# OBC_manufactured.net
KiCad netlist of a schematic drawn in EAGLE
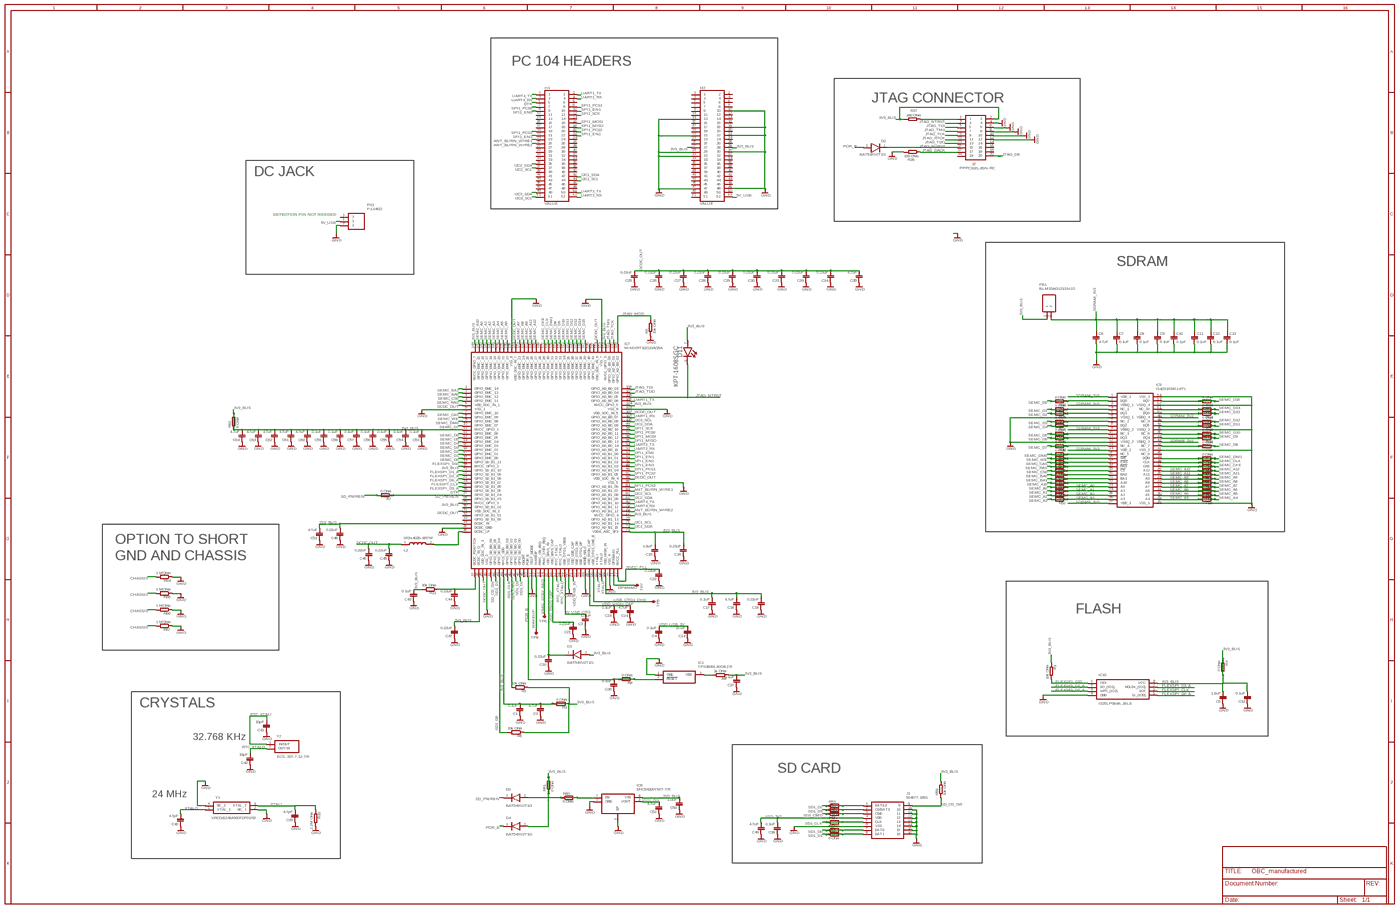
[diagram p0: schematic, sheet 1, overview]
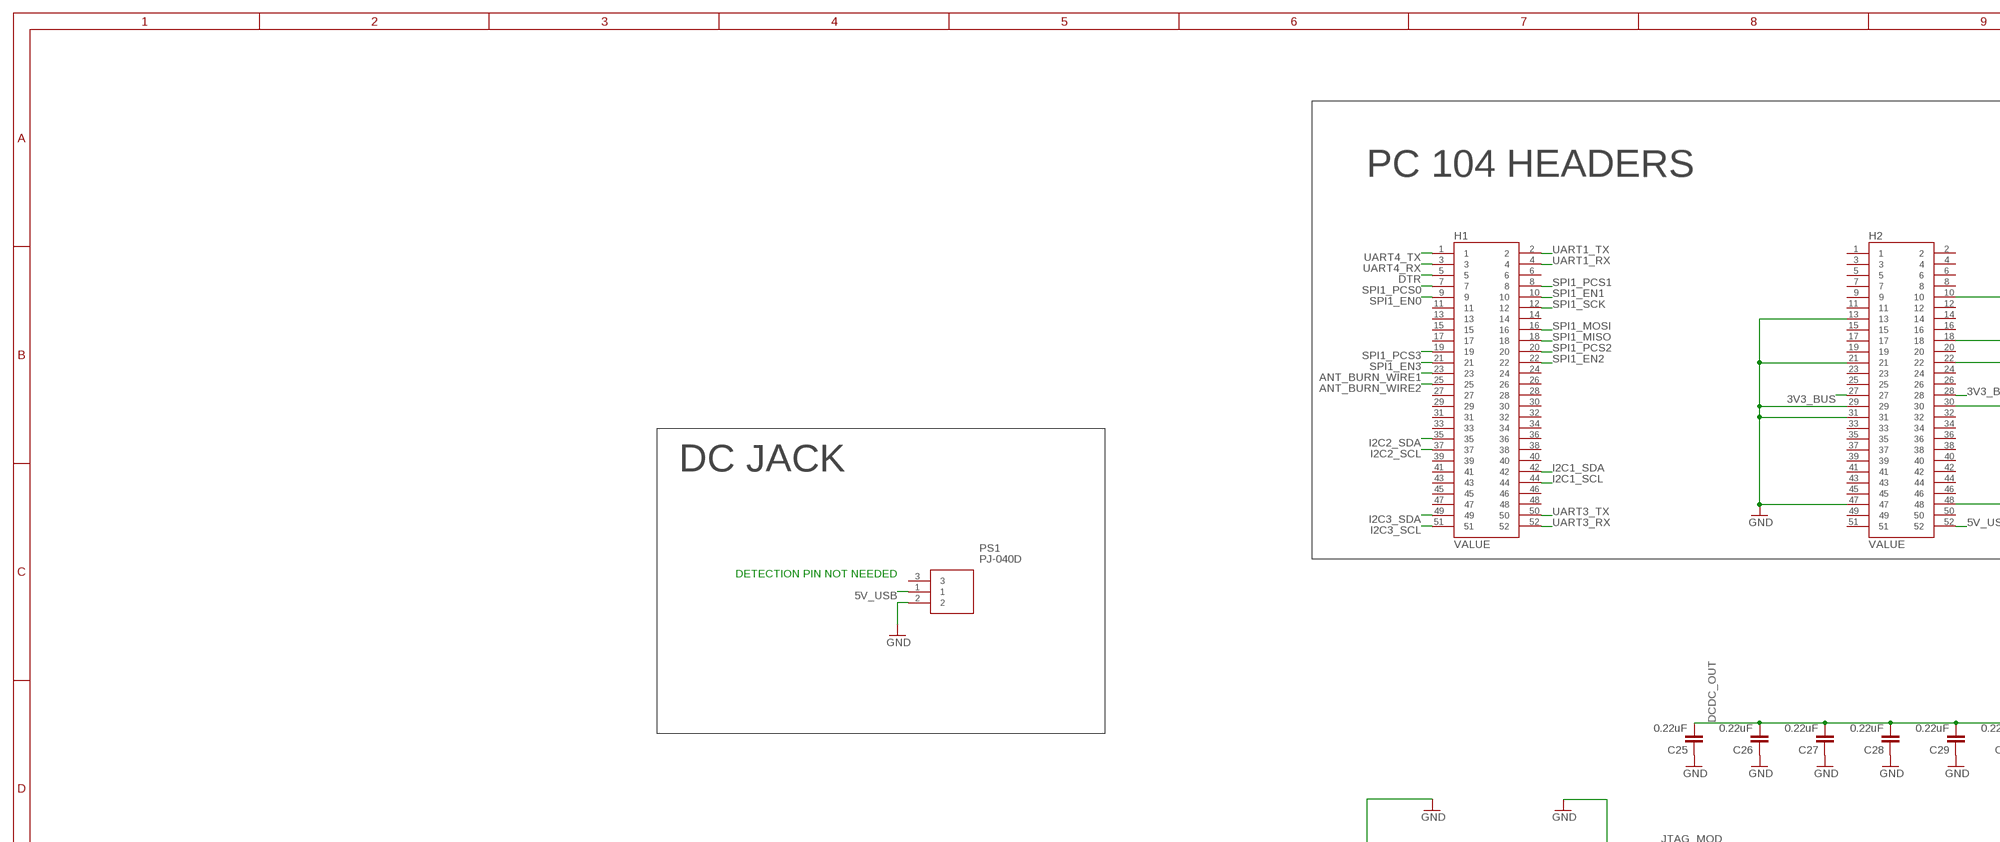
[diagram p1: schematic, sheet 1, part 1 of 4]
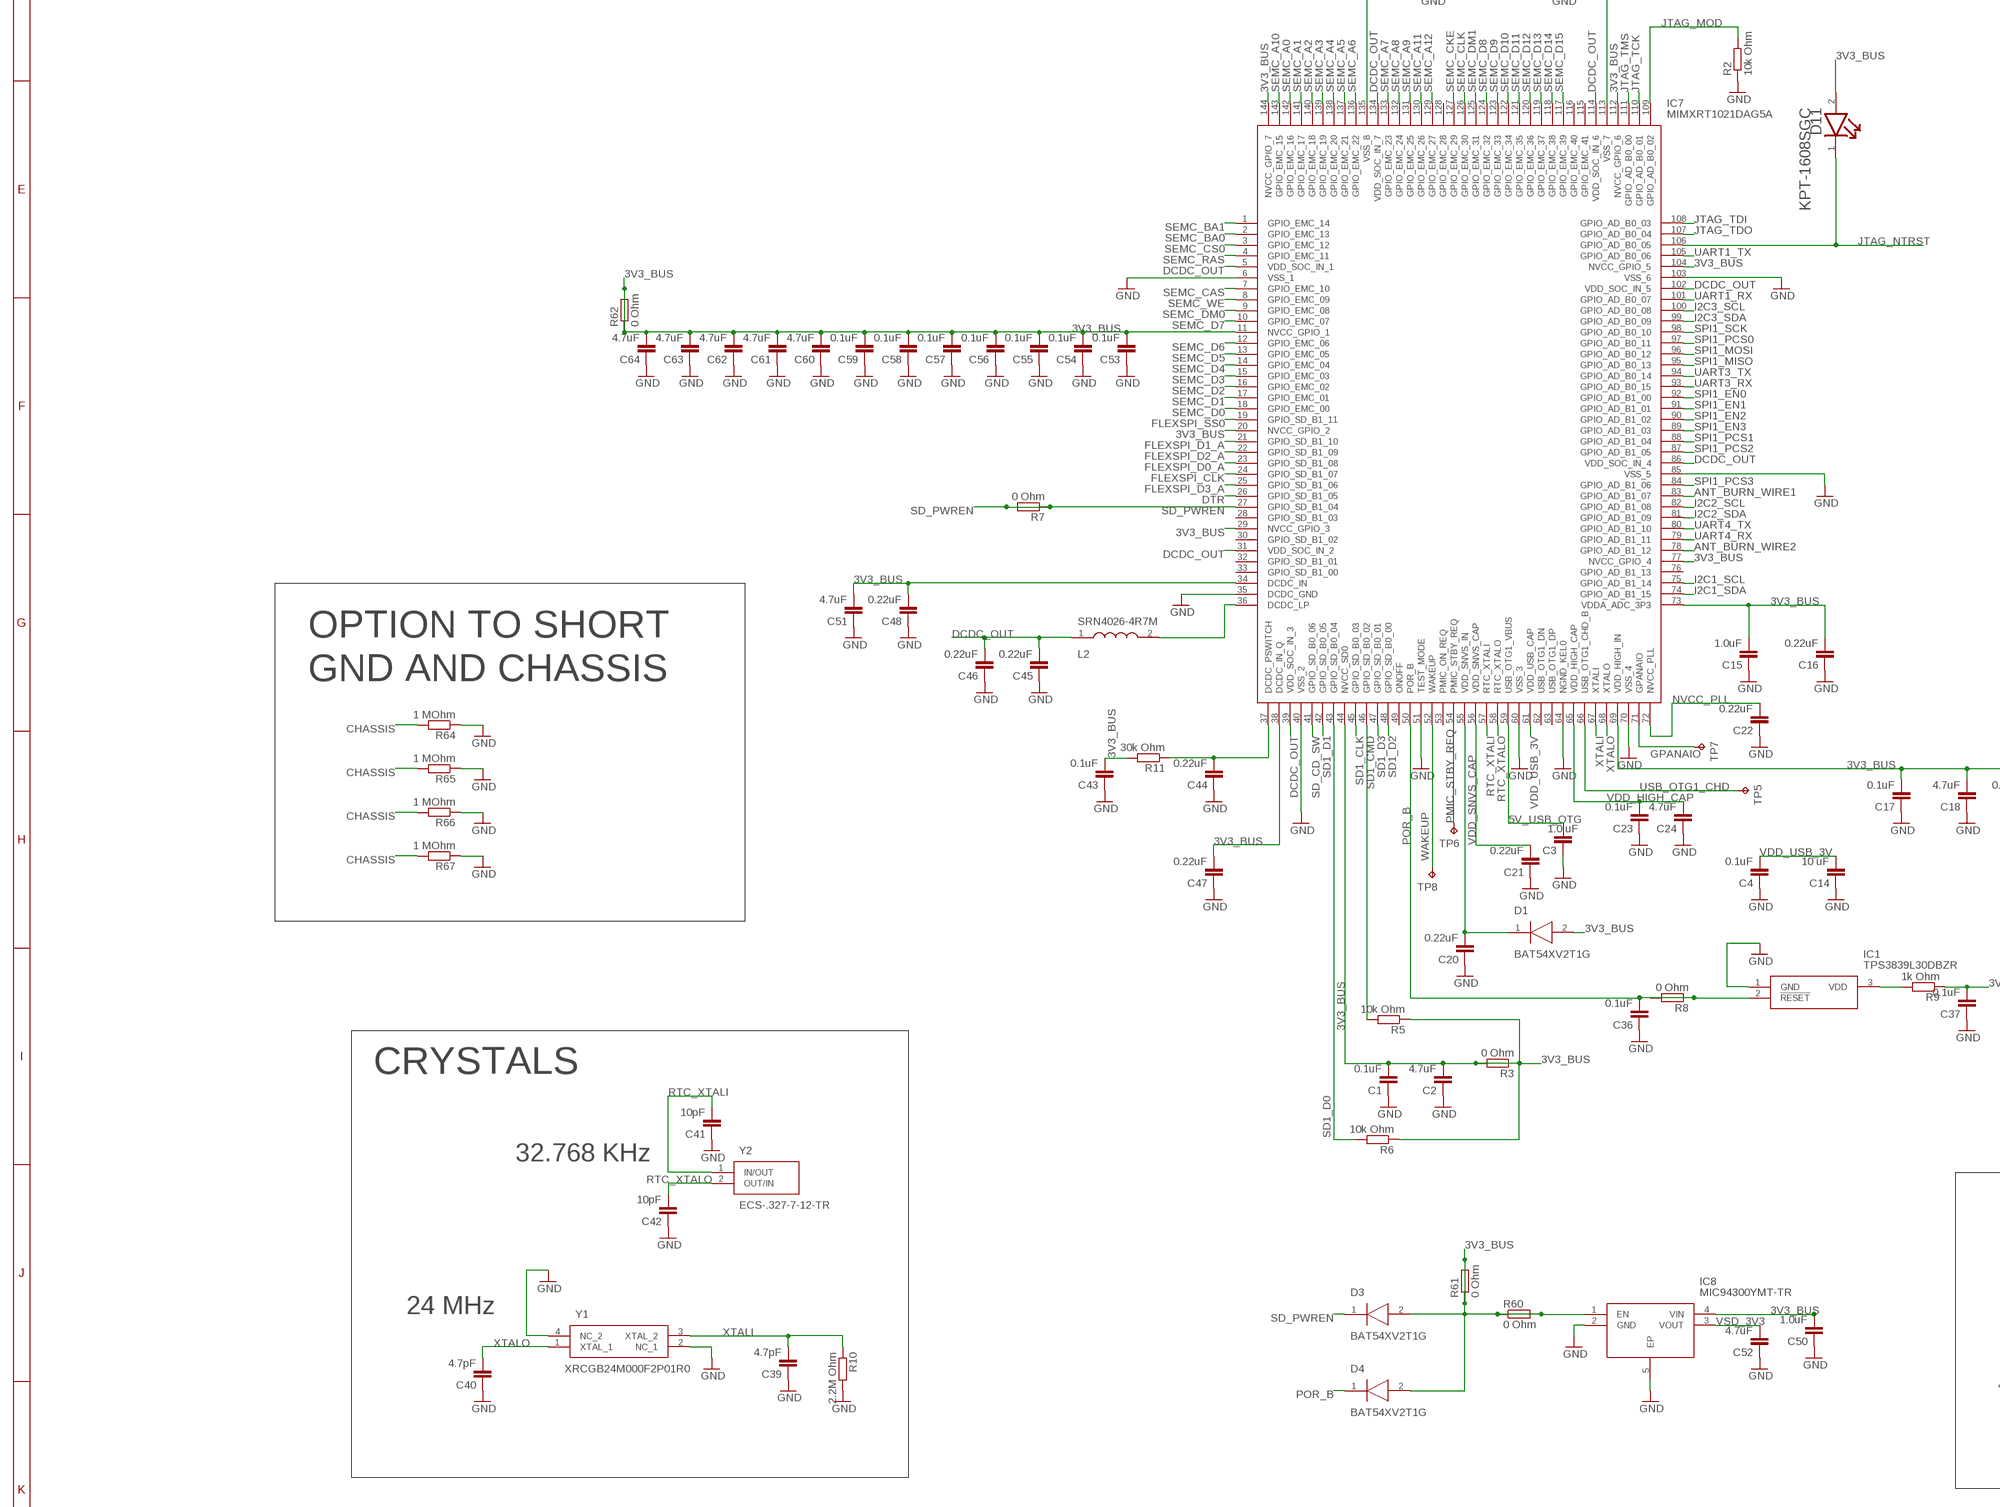
[diagram p2: schematic, sheet 1, part 2 of 4]
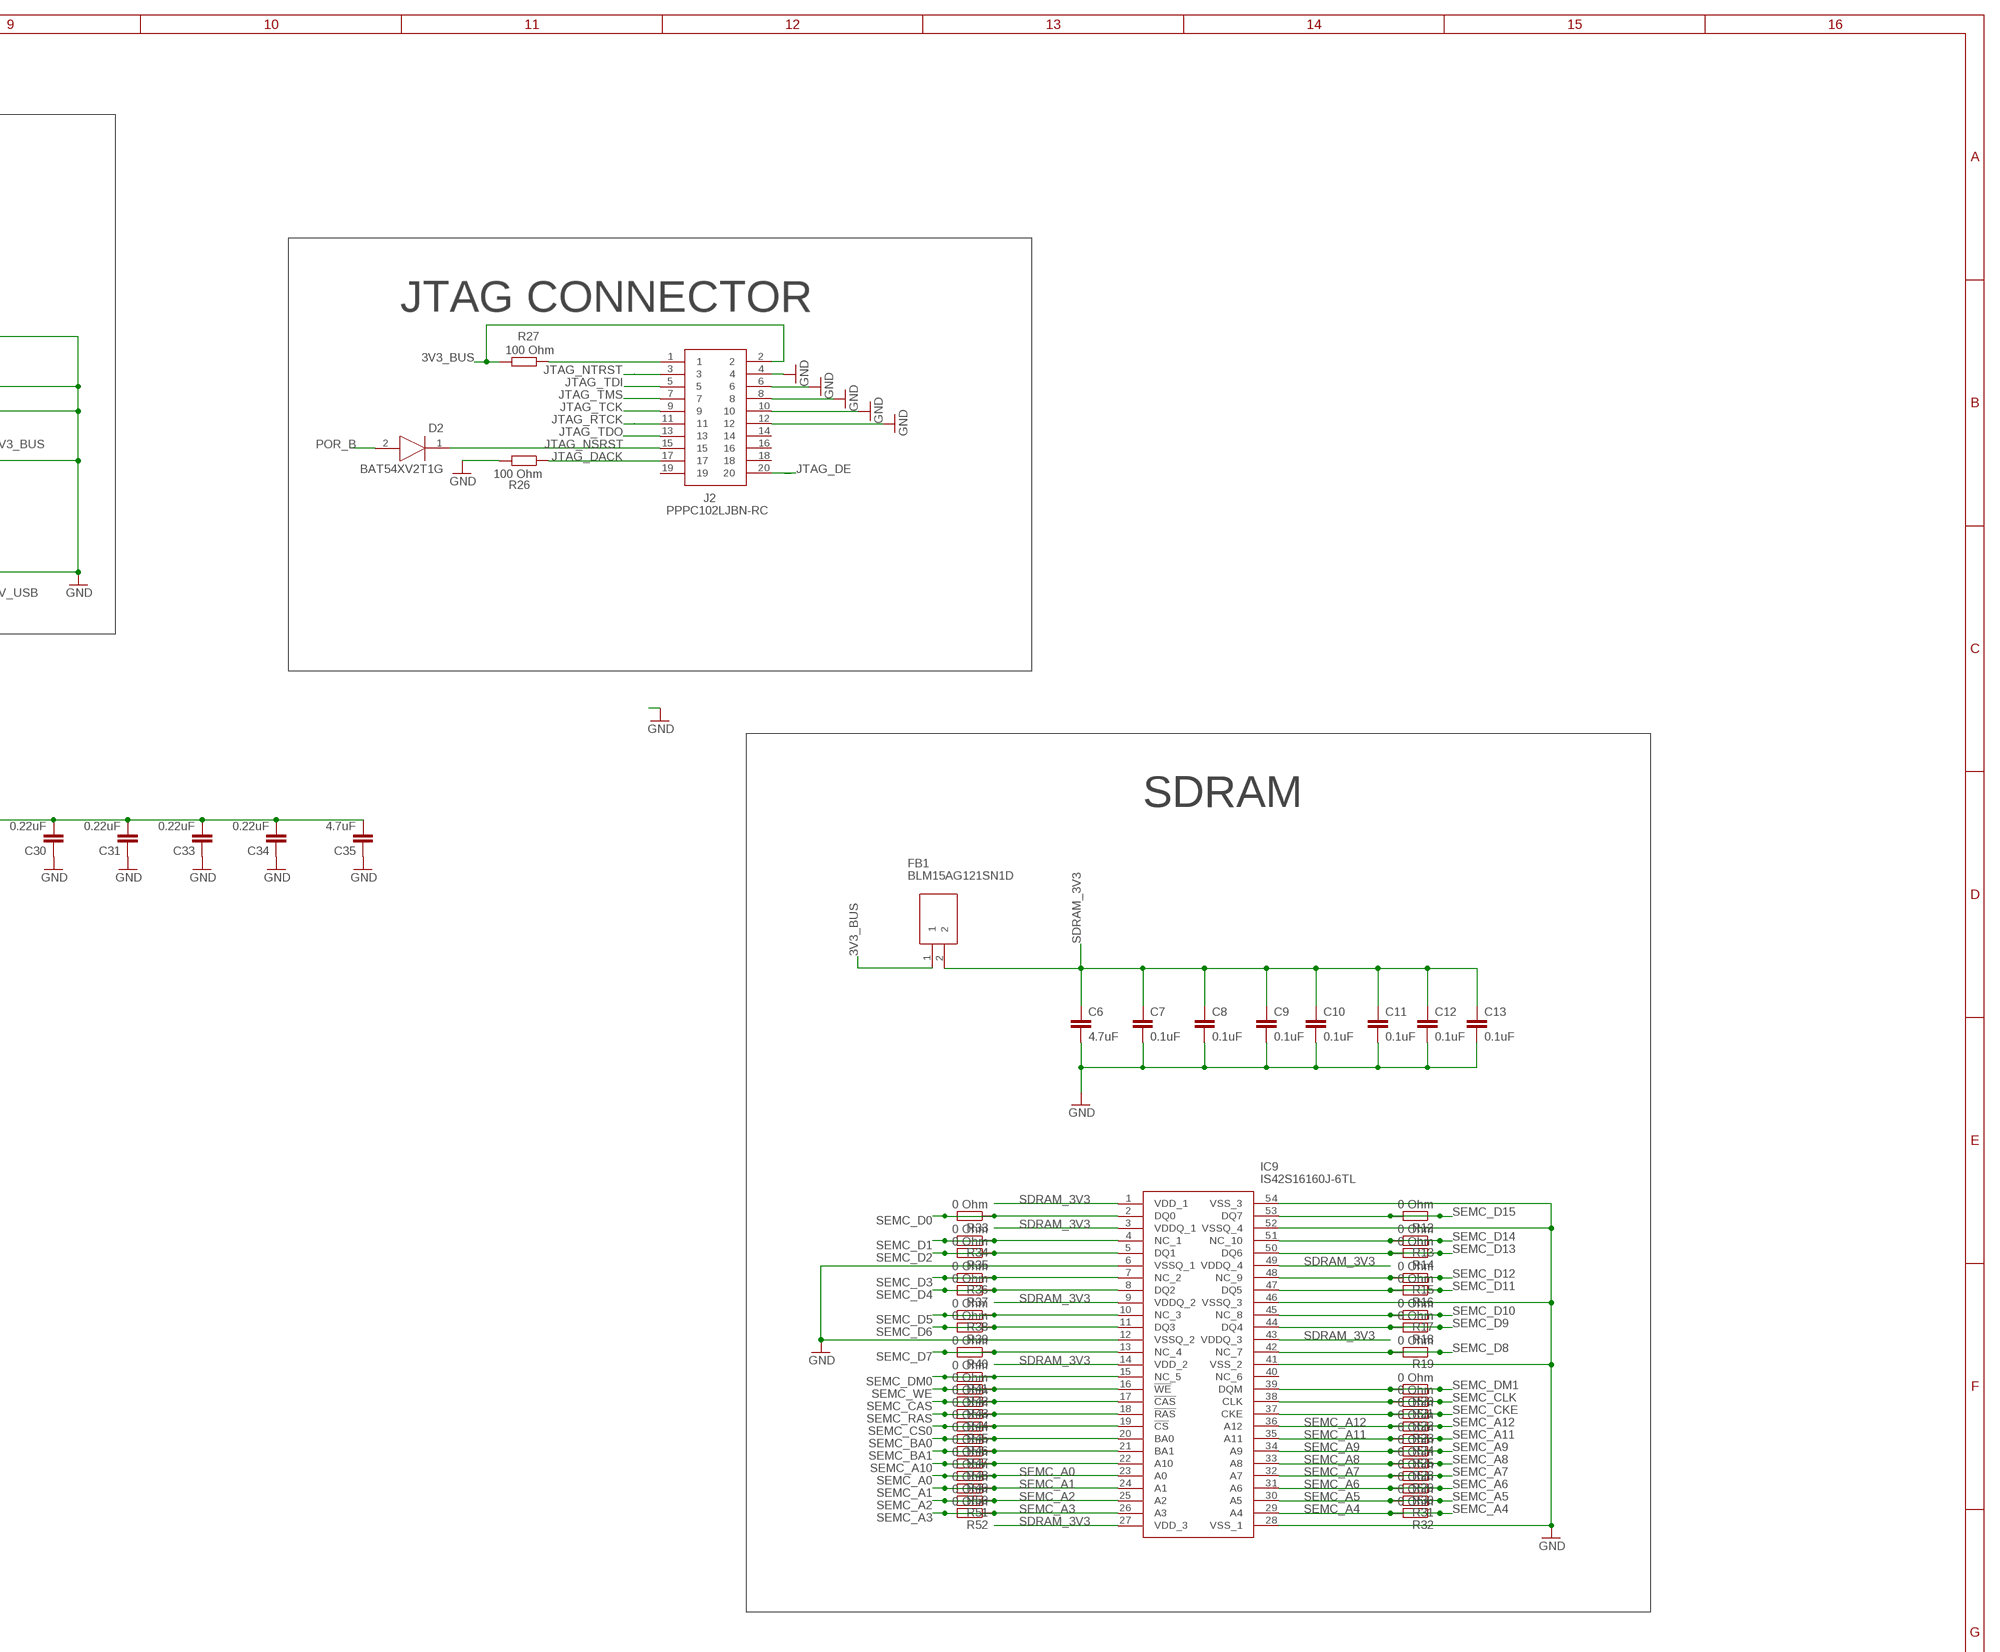
[diagram p3: schematic, sheet 1, part 3 of 4]
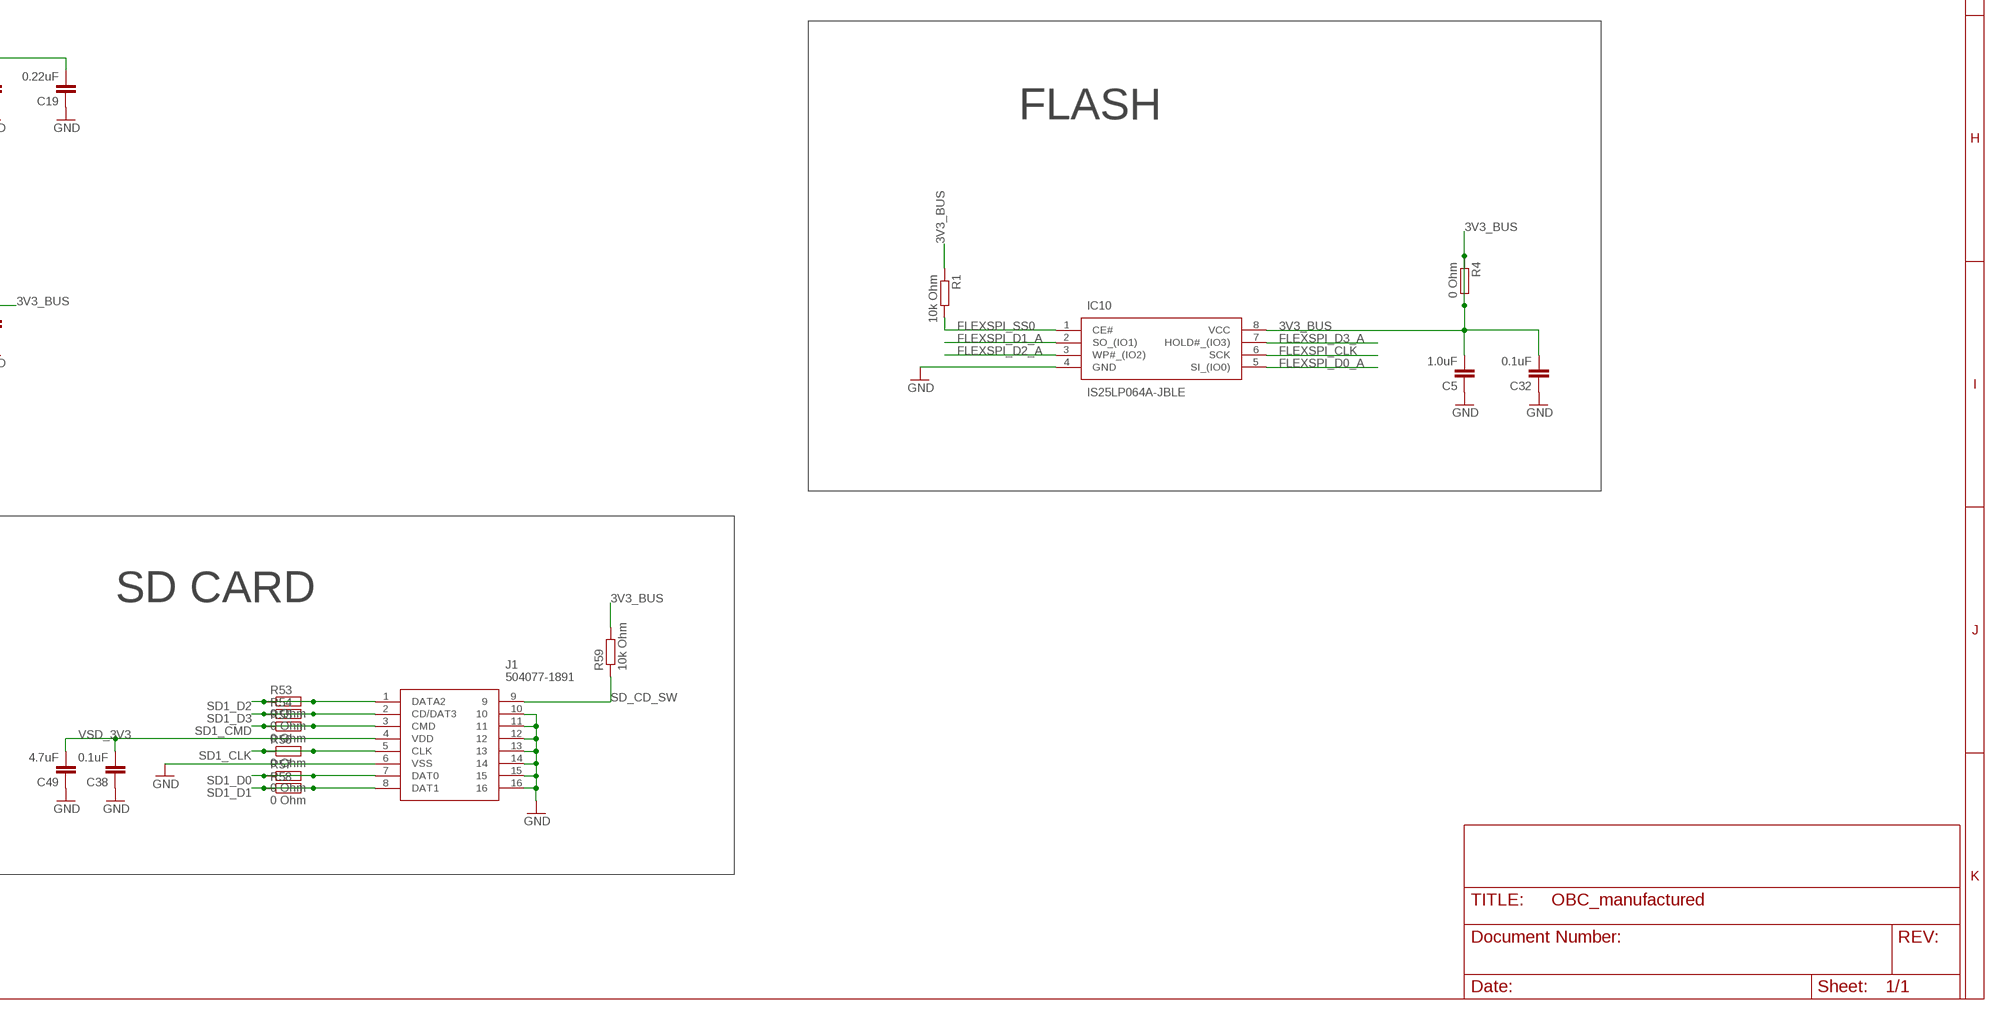
[diagram p4: schematic, sheet 1, part 4 of 4]

(export (version "E")
  (design (tool "Eeschema 10.0.6"))
  (components
    (comp (ref "C1")
      (value "0.1uF")
      (footprint "eagle-import:C0402K")
      (libsource (lib "eagle-import") (part "C-EUC0402K"))
    )
    (comp (ref "C2")
      (value "4.7uF")
      (footprint "eagle-import:C0402K")
      (libsource (lib "eagle-import") (part "C-EUC0402K"))
    )
    (comp (ref "C3")
      (value "1.0 uF")
      (footprint "eagle-import:C0402K")
      (libsource (lib "eagle-import") (part "C-EUC0402K"))
    )
    (comp (ref "C4")
      (value "0.1uF")
      (footprint "eagle-import:C0402K")
      (libsource (lib "eagle-import") (part "C-EUC0402K"))
    )
    (comp (ref "C5")
      (value "1.0uF")
      (footprint "eagle-import:C0402K")
      (libsource (lib "eagle-import") (part "C-EUC0402K"))
    )
    (comp (ref "C6")
      (value "4.7uF")
      (footprint "eagle-import:C0402K")
      (libsource (lib "eagle-import") (part "C-EUC0402K"))
    )
    (comp (ref "C7")
      (value "0.1uF")
      (footprint "eagle-import:C0402K")
      (libsource (lib "eagle-import") (part "C-EUC0402K"))
    )
    (comp (ref "C8")
      (value "0.1uF")
      (footprint "eagle-import:C0402K")
      (libsource (lib "eagle-import") (part "C-EUC0402K"))
    )
    (comp (ref "C9")
      (value "0.1uF")
      (footprint "eagle-import:C0402K")
      (libsource (lib "eagle-import") (part "C-EUC0402K"))
    )
    (comp (ref "C10")
      (value "0.1uF")
      (footprint "eagle-import:C0402K")
      (libsource (lib "eagle-import") (part "C-EUC0402K"))
    )
    (comp (ref "C11")
      (value "0.1uF")
      (footprint "eagle-import:C0402K")
      (libsource (lib "eagle-import") (part "C-EUC0402K"))
    )
    (comp (ref "C12")
      (value "0.1uF")
      (footprint "eagle-import:C0402K")
      (libsource (lib "eagle-import") (part "C-EUC0402K"))
    )
    (comp (ref "C13")
      (value "0.1uF")
      (footprint "eagle-import:C0402K")
      (libsource (lib "eagle-import") (part "C-EUC0402K"))
    )
    (comp (ref "C14")
      (value "10 uF")
      (footprint "eagle-import:C0402K")
      (libsource (lib "eagle-import") (part "C-EUC0402K"))
    )
    (comp (ref "C15")
      (value "1.0uF")
      (footprint "eagle-import:C0402K")
      (libsource (lib "eagle-import") (part "C-EUC0402K"))
    )
    (comp (ref "C16")
      (value "0.22uF")
      (footprint "eagle-import:C0402K")
      (libsource (lib "eagle-import") (part "C-EUC0402K"))
    )
    (comp (ref "C17")
      (value "0.1uF")
      (footprint "eagle-import:C0402K")
      (libsource (lib "eagle-import") (part "C-EUC0402K"))
    )
    (comp (ref "C18")
      (value "4.7uF")
      (footprint "eagle-import:C0402K")
      (libsource (lib "eagle-import") (part "C-EUC0402K"))
    )
    (comp (ref "C19")
      (value "0.22uF")
      (footprint "eagle-import:C0402K")
      (libsource (lib "eagle-import") (part "C-EUC0402K"))
    )
    (comp (ref "C20")
      (value "0.22uF")
      (footprint "eagle-import:C0402K")
      (libsource (lib "eagle-import") (part "C-EUC0402K"))
    )
    (comp (ref "C21")
      (value "0.22uF")
      (footprint "eagle-import:C0402K")
      (libsource (lib "eagle-import") (part "C-EUC0402K"))
    )
    (comp (ref "C22")
      (value "0.22uF")
      (footprint "eagle-import:C0402K")
      (libsource (lib "eagle-import") (part "C-EUC0402K"))
    )
    (comp (ref "C23")
      (value "0.1uF")
      (footprint "eagle-import:C0402K")
      (libsource (lib "eagle-import") (part "C-EUC0402K"))
    )
    (comp (ref "C24")
      (value "4.7uF")
      (footprint "eagle-import:C0402K")
      (libsource (lib "eagle-import") (part "C-EUC0402K"))
    )
    (comp (ref "C25")
      (value "0.22uF")
      (footprint "eagle-import:C0402K")
      (libsource (lib "eagle-import") (part "C-EUC0402K"))
    )
    (comp (ref "C26")
      (value "0.22uF")
      (footprint "eagle-import:C0402K")
      (libsource (lib "eagle-import") (part "C-EUC0402K"))
    )
    (comp (ref "C27")
      (value "0.22uF")
      (footprint "eagle-import:C0402K")
      (libsource (lib "eagle-import") (part "C-EUC0402K"))
    )
    (comp (ref "C28")
      (value "0.22uF")
      (footprint "eagle-import:C0402K")
      (libsource (lib "eagle-import") (part "C-EUC0402K"))
    )
    (comp (ref "C29")
      (value "0.22uF")
      (footprint "eagle-import:C0402K")
      (libsource (lib "eagle-import") (part "C-EUC0402K"))
    )
    (comp (ref "C30")
      (value "0.22uF")
      (footprint "eagle-import:C0402K")
      (libsource (lib "eagle-import") (part "C-EUC0402K"))
    )
    (comp (ref "C31")
      (value "0.22uF")
      (footprint "eagle-import:C0402K")
      (libsource (lib "eagle-import") (part "C-EUC0402K"))
    )
    (comp (ref "C32")
      (value "0.1uF")
      (footprint "eagle-import:C0402K")
      (libsource (lib "eagle-import") (part "C-EUC0402K"))
    )
    (comp (ref "C33")
      (value "0.22uF")
      (footprint "eagle-import:C0402K")
      (libsource (lib "eagle-import") (part "C-EUC0402K"))
    )
    (comp (ref "C34")
      (value "0.22uF")
      (footprint "eagle-import:C0402K")
      (libsource (lib "eagle-import") (part "C-EUC0402K"))
    )
    (comp (ref "C35")
      (value "4.7uF")
      (footprint "eagle-import:C0402K")
      (libsource (lib "eagle-import") (part "C-EUC0402K"))
    )
    (comp (ref "C36")
      (value "0.1uF")
      (footprint "eagle-import:C0402K")
      (libsource (lib "eagle-import") (part "C-EUC0402K"))
    )
    (comp (ref "C37")
      (value "0.1uF")
      (footprint "eagle-import:C0402K")
      (libsource (lib "eagle-import") (part "C-EUC0402K"))
    )
    (comp (ref "C38")
      (value "0.1uF")
      (footprint "eagle-import:C0402K")
      (libsource (lib "eagle-import") (part "C-EUC0402K"))
    )
    (comp (ref "C39")
      (value "4.7pF")
      (footprint "eagle-import:C0402K")
      (libsource (lib "eagle-import") (part "C-EUC0402K"))
    )
    (comp (ref "C40")
      (value "4.7pF")
      (footprint "eagle-import:C0402K")
      (libsource (lib "eagle-import") (part "C-EUC0402K"))
    )
    (comp (ref "C41")
      (value "10pF")
      (footprint "eagle-import:C0402K")
      (libsource (lib "eagle-import") (part "C-EUC0402K"))
    )
    (comp (ref "C42")
      (value "10pF")
      (footprint "eagle-import:C0402K")
      (libsource (lib "eagle-import") (part "C-EUC0402K"))
    )
    (comp (ref "C43")
      (value "0.1uF")
      (footprint "eagle-import:C0402K")
      (libsource (lib "eagle-import") (part "C-EUC0402K"))
    )
    (comp (ref "C44")
      (value "0.22uF")
      (footprint "eagle-import:C0402K")
      (libsource (lib "eagle-import") (part "C-EUC0402K"))
    )
    (comp (ref "C45")
      (value "0.22uF")
      (footprint "eagle-import:C0402K")
      (libsource (lib "eagle-import") (part "C-EUC0402K"))
    )
    (comp (ref "C46")
      (value "0.22uF")
      (footprint "eagle-import:C0402K")
      (libsource (lib "eagle-import") (part "C-EUC0402K"))
    )
    (comp (ref "C47")
      (value "0.22uF")
      (footprint "eagle-import:C0402K")
      (libsource (lib "eagle-import") (part "C-EUC0402K"))
    )
    (comp (ref "C48")
      (value "0.22uF")
      (footprint "eagle-import:C0402K")
      (libsource (lib "eagle-import") (part "C-EUC0402K"))
    )
    (comp (ref "C49")
      (value "4.7uF")
      (footprint "eagle-import:C0402K")
      (libsource (lib "eagle-import") (part "C-EUC0402K"))
    )
    (comp (ref "C50")
      (value "1.0uF")
      (footprint "eagle-import:C0402K")
      (libsource (lib "eagle-import") (part "C-EUC0402K"))
    )
    (comp (ref "C51")
      (value "4.7uF")
      (footprint "eagle-import:C0402K")
      (libsource (lib "eagle-import") (part "C-EUC0402K"))
    )
    (comp (ref "C52")
      (value "4.7uF")
      (footprint "eagle-import:C0402K")
      (libsource (lib "eagle-import") (part "C-EUC0402K"))
    )
    (comp (ref "C53")
      (value "0.1uF")
      (footprint "eagle-import:C0402K")
      (libsource (lib "eagle-import") (part "C-EUC0402K"))
    )
    (comp (ref "C54")
      (value "0.1uF")
      (footprint "eagle-import:C0402K")
      (libsource (lib "eagle-import") (part "C-EUC0402K"))
    )
    (comp (ref "C55")
      (value "0.1uF")
      (footprint "eagle-import:C0402K")
      (libsource (lib "eagle-import") (part "C-EUC0402K"))
    )
    (comp (ref "C56")
      (value "0.1uF")
      (footprint "eagle-import:C0402K")
      (libsource (lib "eagle-import") (part "C-EUC0402K"))
    )
    (comp (ref "C57")
      (value "0.1uF")
      (footprint "eagle-import:C0402K")
      (libsource (lib "eagle-import") (part "C-EUC0402K"))
    )
    (comp (ref "C58")
      (value "0.1uF")
      (footprint "eagle-import:C0402K")
      (libsource (lib "eagle-import") (part "C-EUC0402K"))
    )
    (comp (ref "C59")
      (value "0.1uF")
      (footprint "eagle-import:C0402K")
      (libsource (lib "eagle-import") (part "C-EUC0402K"))
    )
    (comp (ref "C60")
      (value "4.7uF")
      (footprint "eagle-import:C0402K")
      (libsource (lib "eagle-import") (part "C-EUC0402K"))
    )
    (comp (ref "C61")
      (value "4.7uF")
      (footprint "eagle-import:C0402K")
      (libsource (lib "eagle-import") (part "C-EUC0402K"))
    )
    (comp (ref "C62")
      (value "4.7uF")
      (footprint "eagle-import:C0402K")
      (libsource (lib "eagle-import") (part "C-EUC0402K"))
    )
    (comp (ref "C63")
      (value "4.7uF")
      (footprint "eagle-import:C0402K")
      (libsource (lib "eagle-import") (part "C-EUC0402K"))
    )
    (comp (ref "C64")
      (value "4.7uF")
      (footprint "eagle-import:C0402K")
      (libsource (lib "eagle-import") (part "C-EUC0402K"))
    )
    (comp (ref "D1")
      (value "BAT54XV2T1G")
      (footprint "eagle-import:SODFL1608X70N")
      (fields (field (name "MOUSER_PART_NUMBER") "863-BAT54XV2T1G"))
      (libsource (lib "eagle-import") (part "BAT54XV2T1G"))
    )
    (comp (ref "D2")
      (value "BAT54XV2T1G")
      (footprint "eagle-import:SODFL1608X70N")
      (fields (field (name "MOUSER_PART_NUMBER") "863-BAT54XV2T1G"))
      (libsource (lib "eagle-import") (part "BAT54XV2T1G"))
    )
    (comp (ref "D3")
      (value "BAT54XV2T1G")
      (footprint "eagle-import:SODFL1608X70N")
      (fields (field (name "MOUSER_PART_NUMBER") "863-BAT54XV2T1G"))
      (libsource (lib "eagle-import") (part "BAT54XV2T1G"))
    )
    (comp (ref "D4")
      (value "BAT54XV2T1G")
      (footprint "eagle-import:SODFL1608X70N")
      (fields (field (name "MOUSER_PART_NUMBER") "863-BAT54XV2T1G"))
      (libsource (lib "eagle-import") (part "BAT54XV2T1G"))
    )
    (comp (ref "D11")
      (value "KINGBRIGHT_KPT-1608SGCKINGBRIGHT_KPT-1608SGC_0_0")
      (footprint "eagle-import:KINGBRIGHT_KPT-1608SGC_0")
      (fields (field (name "MF") "Kingbright") (field (name "MPN") "KPT-1608SGC"))
      (libsource (lib "eagle-import") (part "KINGBRIGHT_KPT-1608SGCKINGBRIGHT_KPT-1608SGC_0_0"))
    )
    (comp (ref "FB1")
      (value "BLM15AG121SN1D")
      (footprint "eagle-import:NFZ15SG152SN10B")
      (fields (field (name "MOUSER_PART_NUMBER") "81-BLM15AG121SN1D"))
      (libsource (lib "eagle-import") (part "BLM15AG121SN1D"))
    )
    (comp (ref "H1")
      (value "ESQ-126-39-G-D")
      (footprint "eagle-import:SAMTEC_ESQ-126-39-G-D")
      (fields (field (name "DIGI-KEY_PART_NUMBER") "SAM10462-ND") (field (name "MF") "Samtec"))
      (libsource (lib "eagle-import") (part "ESQ-126-39-G-D"))
    )
    (comp (ref "H2")
      (value "ESQ-126-39-G-D")
      (footprint "eagle-import:SAMTEC_ESQ-126-39-G-D")
      (fields (field (name "DIGI-KEY_PART_NUMBER") "SAM10462-ND") (field (name "MF") "Samtec"))
      (libsource (lib "eagle-import") (part "ESQ-126-39-G-D"))
    )
    (comp (ref "IC1")
      (value "TPS3839L30DBZR")
      (footprint "eagle-import:SOT95P237X112-3N")
      (fields (field (name "MOUSER_PART_NUMBER") "595-TPS3839L30DBZR"))
      (libsource (lib "eagle-import") (part "TPS3839L30DBZR"))
    )
    (comp (ref "IC7")
      (value "MIMXRT1021DAG5A")
      (footprint "eagle-import:QFP50P2200X2200X160-144N")
      (fields (field (name "MOUSER_PART_NUMBER") "771-MIMXRT1021DAG5A"))
      (libsource (lib "eagle-import") (part "MIMXRT1021DAG5A"))
    )
    (comp (ref "IC8")
      (value "MIC94300YMT-TR")
      (footprint "eagle-import:SON50P160X120X60-5N")
      (fields (field (name "MOUSER_PART_NUMBER") "998-MIC94300YMTTR"))
      (libsource (lib "eagle-import") (part "MIC94300YMT-TR"))
    )
    (comp (ref "IC9")
      (value "IS42S16160J-6TL")
      (footprint "eagle-import:SOP80P1176X120-54N")
      (fields (field (name "MOUSER_PART_NUMBER") "870-IS42S16160J-6TL"))
      (libsource (lib "eagle-import") (part "IS42S16160J-6TL"))
    )
    (comp (ref "IC10")
      (value "IS25LP064A-JBLE")
      (footprint "eagle-import:SOIC127P790X216-8N")
      (libsource (lib "eagle-import") (part "IS25LP064A-JBLE"))
    )
    (comp (ref "J1")
      (value "504077-1891")
      (footprint "eagle-import:5040771891")
      (fields (field (name "MOUSER_PART_NUMBER") "538-504077-1891"))
      (libsource (lib "eagle-import") (part "504077-1891"))
    )
    (comp (ref "J2")
      (value "PPPC102LJBN-RC")
      (footprint "eagle-import:RHDRRA20W60P254X254_2X10_2590X")
      (libsource (lib "eagle-import") (part "PPPC102LJBN-RC"))
    )
    (comp (ref "L2")
      (value "SRN4026-4R7M")
      (footprint "eagle-import:SRN4026")
      (fields (field (name "MOUSER_PART_NUMBER") "652-SRN4026-4R7M"))
      (libsource (lib "eagle-import") (part "SRN4026-4R7M"))
    )
    (comp (ref "PS1")
      (value "PJ-040D")
      (footprint "eagle-import:PJ040D")
      (fields (field (name "MOUSER_PART_NUMBER") "490-PJ-040D"))
      (libsource (lib "eagle-import") (part "PJ-040D"))
    )
    (comp (ref "R1")
      (value "10k Ohm")
      (footprint "eagle-import:R0402")
      (libsource (lib "eagle-import") (part "R-EU_R0402"))
    )
    (comp (ref "R2")
      (value "10k Ohm")
      (footprint "eagle-import:R0402")
      (libsource (lib "eagle-import") (part "R-EU_R0402"))
    )
    (comp (ref "R3")
      (value "0 Ohm")
      (footprint "eagle-import:R0402")
      (libsource (lib "eagle-import") (part "R-EU_R0402"))
    )
    (comp (ref "R4")
      (value "0 Ohm")
      (footprint "eagle-import:R0402")
      (libsource (lib "eagle-import") (part "R-EU_R0402"))
    )
    (comp (ref "R5")
      (value "10k Ohm")
      (footprint "eagle-import:R0402")
      (libsource (lib "eagle-import") (part "R-EU_R0402"))
    )
    (comp (ref "R6")
      (value "10k Ohm")
      (footprint "eagle-import:R0402")
      (libsource (lib "eagle-import") (part "R-EU_R0402"))
    )
    (comp (ref "R7")
      (value "0 Ohm")
      (footprint "eagle-import:R0402")
      (libsource (lib "eagle-import") (part "R-EU_R0402"))
    )
    (comp (ref "R8")
      (value "0 Ohm")
      (footprint "eagle-import:R0402")
      (libsource (lib "eagle-import") (part "R-EU_R0402"))
    )
    (comp (ref "R9")
      (value "1k Ohm")
      (footprint "eagle-import:R0402")
      (libsource (lib "eagle-import") (part "R-EU_R0402"))
    )
    (comp (ref "R10")
      (value "2.2M Ohm")
      (footprint "eagle-import:R0402")
      (libsource (lib "eagle-import") (part "R-EU_R0402"))
    )
    (comp (ref "R11")
      (value "30k Ohm")
      (footprint "eagle-import:R0402")
      (libsource (lib "eagle-import") (part "R-EU_R0402"))
    )
    (comp (ref "R12")
      (value "0 Ohm")
      (footprint "eagle-import:R0402")
      (libsource (lib "eagle-import") (part "R-EU_R0402"))
    )
    (comp (ref "R13")
      (value "0 Ohm")
      (footprint "eagle-import:R0402")
      (libsource (lib "eagle-import") (part "R-EU_R0402"))
    )
    (comp (ref "R14")
      (value "0 Ohm")
      (footprint "eagle-import:R0402")
      (libsource (lib "eagle-import") (part "R-EU_R0402"))
    )
    (comp (ref "R15")
      (value "0 Ohm")
      (footprint "eagle-import:R0402")
      (libsource (lib "eagle-import") (part "R-EU_R0402"))
    )
    (comp (ref "R16")
      (value "0 Ohm")
      (footprint "eagle-import:R0402")
      (libsource (lib "eagle-import") (part "R-EU_R0402"))
    )
    (comp (ref "R17")
      (value "0 Ohm")
      (footprint "eagle-import:R0402")
      (libsource (lib "eagle-import") (part "R-EU_R0402"))
    )
    (comp (ref "R18")
      (value "0 Ohm")
      (footprint "eagle-import:R0402")
      (libsource (lib "eagle-import") (part "R-EU_R0402"))
    )
    (comp (ref "R19")
      (value "0 Ohm")
      (footprint "eagle-import:R0402")
      (libsource (lib "eagle-import") (part "R-EU_R0402"))
    )
    (comp (ref "R20")
      (value "0 Ohm")
      (footprint "eagle-import:R0402")
      (libsource (lib "eagle-import") (part "R-EU_R0402"))
    )
    (comp (ref "R21")
      (value "0 Ohm")
      (footprint "eagle-import:R0402")
      (libsource (lib "eagle-import") (part "R-EU_R0402"))
    )
    (comp (ref "R22")
      (value "0 Ohm")
      (footprint "eagle-import:R0402")
      (libsource (lib "eagle-import") (part "R-EU_R0402"))
    )
    (comp (ref "R23")
      (value "0 Ohm")
      (footprint "eagle-import:R0402")
      (libsource (lib "eagle-import") (part "R-EU_R0402"))
    )
    (comp (ref "R24")
      (value "0 Ohm")
      (footprint "eagle-import:R0402")
      (libsource (lib "eagle-import") (part "R-EU_R0402"))
    )
    (comp (ref "R25")
      (value "0 Ohm")
      (footprint "eagle-import:R0402")
      (libsource (lib "eagle-import") (part "R-EU_R0402"))
    )
    (comp (ref "R26")
      (value "100 Ohm")
      (footprint "eagle-import:R0402")
      (libsource (lib "eagle-import") (part "R-EU_R0402"))
    )
    (comp (ref "R27")
      (value "100 Ohm")
      (footprint "eagle-import:R0402")
      (libsource (lib "eagle-import") (part "R-EU_R0402"))
    )
    (comp (ref "R28")
      (value "0 Ohm")
      (footprint "eagle-import:R0402")
      (libsource (lib "eagle-import") (part "R-EU_R0402"))
    )
    (comp (ref "R29")
      (value "0 Ohm")
      (footprint "eagle-import:R0402")
      (libsource (lib "eagle-import") (part "R-EU_R0402"))
    )
    (comp (ref "R30")
      (value "0 Ohm")
      (footprint "eagle-import:R0402")
      (libsource (lib "eagle-import") (part "R-EU_R0402"))
    )
    (comp (ref "R31")
      (value "0 Ohm")
      (footprint "eagle-import:R0402")
      (libsource (lib "eagle-import") (part "R-EU_R0402"))
    )
    (comp (ref "R32")
      (value "0 Ohm")
      (footprint "eagle-import:R0402")
      (libsource (lib "eagle-import") (part "R-EU_R0402"))
    )
    (comp (ref "R33")
      (value "0 Ohm")
      (footprint "eagle-import:R0402")
      (libsource (lib "eagle-import") (part "R-EU_R0402"))
    )
    (comp (ref "R34")
      (value "0 Ohm")
      (footprint "eagle-import:R0402")
      (libsource (lib "eagle-import") (part "R-EU_R0402"))
    )
    (comp (ref "R35")
      (value "0 Ohm")
      (footprint "eagle-import:R0402")
      (libsource (lib "eagle-import") (part "R-EU_R0402"))
    )
    (comp (ref "R36")
      (value "0 Ohm")
      (footprint "eagle-import:R0402")
      (libsource (lib "eagle-import") (part "R-EU_R0402"))
    )
    (comp (ref "R37")
      (value "0 Ohm")
      (footprint "eagle-import:R0402")
      (libsource (lib "eagle-import") (part "R-EU_R0402"))
    )
    (comp (ref "R38")
      (value "0 Ohm")
      (footprint "eagle-import:R0402")
      (libsource (lib "eagle-import") (part "R-EU_R0402"))
    )
    (comp (ref "R39")
      (value "0 Ohm")
      (footprint "eagle-import:R0402")
      (libsource (lib "eagle-import") (part "R-EU_R0402"))
    )
    (comp (ref "R40")
      (value "0 Ohm")
      (footprint "eagle-import:R0402")
      (libsource (lib "eagle-import") (part "R-EU_R0402"))
    )
    (comp (ref "R41")
      (value "0 Ohm")
      (footprint "eagle-import:R0402")
      (libsource (lib "eagle-import") (part "R-EU_R0402"))
    )
    (comp (ref "R42")
      (value "0 Ohm")
      (footprint "eagle-import:R0402")
      (libsource (lib "eagle-import") (part "R-EU_R0402"))
    )
    (comp (ref "R43")
      (value "0 Ohm")
      (footprint "eagle-import:R0402")
      (libsource (lib "eagle-import") (part "R-EU_R0402"))
    )
    (comp (ref "R44")
      (value "0 Ohm")
      (footprint "eagle-import:R0402")
      (libsource (lib "eagle-import") (part "R-EU_R0402"))
    )
    (comp (ref "R45")
      (value "0 Ohm")
      (footprint "eagle-import:R0402")
      (libsource (lib "eagle-import") (part "R-EU_R0402"))
    )
    (comp (ref "R46")
      (value "0 Ohm")
      (footprint "eagle-import:R0402")
      (libsource (lib "eagle-import") (part "R-EU_R0402"))
    )
    (comp (ref "R47")
      (value "0 Ohm")
      (footprint "eagle-import:R0402")
      (libsource (lib "eagle-import") (part "R-EU_R0402"))
    )
    (comp (ref "R48")
      (value "0 Ohm")
      (footprint "eagle-import:R0402")
      (libsource (lib "eagle-import") (part "R-EU_R0402"))
    )
    (comp (ref "R49")
      (value "0 Ohm")
      (footprint "eagle-import:R0402")
      (libsource (lib "eagle-import") (part "R-EU_R0402"))
    )
    (comp (ref "R50")
      (value "0 Ohm")
      (footprint "eagle-import:R0402")
      (libsource (lib "eagle-import") (part "R-EU_R0402"))
    )
    (comp (ref "R51")
      (value "0 Ohm")
      (footprint "eagle-import:R0402")
      (libsource (lib "eagle-import") (part "R-EU_R0402"))
    )
    (comp (ref "R52")
      (value "0 Ohm")
      (footprint "eagle-import:R0402")
      (libsource (lib "eagle-import") (part "R-EU_R0402"))
    )
    (comp (ref "R53")
      (value "0 Ohm")
      (footprint "eagle-import:R0402")
      (libsource (lib "eagle-import") (part "R-EU_R0402"))
    )
    (comp (ref "R54")
      (value "0 Ohm")
      (footprint "eagle-import:R0402")
      (libsource (lib "eagle-import") (part "R-EU_R0402"))
    )
    (comp (ref "R55")
      (value "0 Ohm")
      (footprint "eagle-import:R0402")
      (libsource (lib "eagle-import") (part "R-EU_R0402"))
    )
    (comp (ref "R56")
      (value "0 Ohm")
      (footprint "eagle-import:R0402")
      (libsource (lib "eagle-import") (part "R-EU_R0402"))
    )
    (comp (ref "R57")
      (value "0 Ohm")
      (footprint "eagle-import:R0402")
      (libsource (lib "eagle-import") (part "R-EU_R0402"))
    )
    (comp (ref "R58")
      (value "0 Ohm")
      (footprint "eagle-import:R0402")
      (libsource (lib "eagle-import") (part "R-EU_R0402"))
    )
    (comp (ref "R59")
      (value "10k Ohm")
      (footprint "eagle-import:R0402")
      (libsource (lib "eagle-import") (part "R-EU_R0402"))
    )
    (comp (ref "R60")
      (value "0 Ohm")
      (footprint "eagle-import:R0402")
      (libsource (lib "eagle-import") (part "R-EU_R0402"))
    )
    (comp (ref "R61")
      (value "0 Ohm")
      (footprint "eagle-import:R0402")
      (libsource (lib "eagle-import") (part "R-EU_R0402"))
    )
    (comp (ref "R62")
      (value "0 Ohm")
      (footprint "eagle-import:R0402")
      (libsource (lib "eagle-import") (part "R-EU_R0402"))
    )
    (comp (ref "R64")
      (value "1 MOhm")
      (footprint "eagle-import:R0805")
      (libsource (lib "eagle-import") (part "R-EU_R0805"))
    )
    (comp (ref "R65")
      (value "1 MOhm")
      (footprint "eagle-import:R0805")
      (libsource (lib "eagle-import") (part "R-EU_R0805"))
    )
    (comp (ref "R66")
      (value "1 MOhm")
      (footprint "eagle-import:R0805")
      (libsource (lib "eagle-import") (part "R-EU_R0805"))
    )
    (comp (ref "R67")
      (value "1 MOhm")
      (footprint "eagle-import:R0805")
      (libsource (lib "eagle-import") (part "R-EU_R0805"))
    )
    (comp (ref "TP5")
      (value "TPTP06R")
      (footprint "eagle-import:TP06R")
      (libsource (lib "eagle-import") (part "TPTP06R"))
    )
    (comp (ref "TP6")
      (value "TPTP06R")
      (footprint "eagle-import:TP06R")
      (libsource (lib "eagle-import") (part "TPTP06R"))
    )
    (comp (ref "TP7")
      (value "TPTP06R")
      (footprint "eagle-import:TP06R")
      (libsource (lib "eagle-import") (part "TPTP06R"))
    )
    (comp (ref "TP8")
      (value "TPTP06R")
      (footprint "eagle-import:TP06R")
      (libsource (lib "eagle-import") (part "TPTP06R"))
    )
    (comp (ref "Y1")
      (value "XRCGB24M000F2P01R0")
      (footprint "eagle-import:XRCGB24M000F2P01R0")
      (fields (field (name "MOUSER_PART_NUMBER") "81-XRCGB24M000F2P01R"))
      (libsource (lib "eagle-import") (part "XRCGB24M000F2P01R0"))
    )
    (comp (ref "Y2")
      (value "ECS-.327-7-12-TR")
      (footprint "eagle-import:ECS327712TR")
      (fields (field (name "MOUSER_PART_NUMBER") "520-ECS-.327-7-12-TR"))
      (libsource (lib "eagle-import") (part "ECS-.327-7-12-TR"))
    )
  )
  (nets
    (net (code "1") (name "/3V3_BUS") (class "Default")
      (node (ref "C1") (pin "2") (pinfunction "2_2") (pintype "passive"))
      (node (ref "C15") (pin "2") (pinfunction "2_2") (pintype "passive"))
      (node (ref "C16") (pin "2") (pinfunction "2_2") (pintype "passive"))
      (node (ref "C17") (pin "2") (pinfunction "2_2") (pintype "passive"))
      (node (ref "C18") (pin "2") (pinfunction "2_2") (pintype "passive"))
      (node (ref "C19") (pin "2") (pinfunction "2_2") (pintype "passive"))
      (node (ref "C2") (pin "2") (pinfunction "2_2") (pintype "passive"))
      (node (ref "C32") (pin "2") (pinfunction "2_2") (pintype "passive"))
      (node (ref "C37") (pin "2") (pinfunction "2_2") (pintype "passive"))
      (node (ref "C43") (pin "2") (pinfunction "2_2") (pintype "passive"))
      (node (ref "C47") (pin "2") (pinfunction "2_2") (pintype "passive"))
      (node (ref "C48") (pin "2") (pinfunction "2_2") (pintype "passive"))
      (node (ref "C5") (pin "2") (pinfunction "2_2") (pintype "passive"))
      (node (ref "C50") (pin "2") (pinfunction "2_2") (pintype "passive"))
      (node (ref "C51") (pin "2") (pinfunction "2_2") (pintype "passive"))
      (node (ref "C53") (pin "2") (pinfunction "2_2") (pintype "passive"))
      (node (ref "C54") (pin "2") (pinfunction "2_2") (pintype "passive"))
      (node (ref "C55") (pin "2") (pinfunction "2_2") (pintype "passive"))
      (node (ref "C56") (pin "2") (pinfunction "2_2") (pintype "passive"))
      (node (ref "C57") (pin "2") (pinfunction "2_2") (pintype "passive"))
      (node (ref "C58") (pin "2") (pinfunction "2_2") (pintype "passive"))
      (node (ref "C59") (pin "2") (pinfunction "2_2") (pintype "passive"))
      (node (ref "C60") (pin "2") (pinfunction "2_2") (pintype "passive"))
      (node (ref "C61") (pin "2") (pinfunction "2_2") (pintype "passive"))
      (node (ref "C62") (pin "2") (pinfunction "2_2") (pintype "passive"))
      (node (ref "C63") (pin "2") (pinfunction "2_2") (pintype "passive"))
      (node (ref "C64") (pin "2") (pinfunction "2_2") (pintype "passive"))
      (node (ref "D1") (pin "2") (pinfunction "A_2") (pintype "bidirectional"))
      (node (ref "D11") (pin "2") (pinfunction "ANODE_2") (pintype "passive"))
      (node (ref "D3") (pin "2") (pinfunction "A_2") (pintype "bidirectional"))
      (node (ref "D4") (pin "2") (pinfunction "A_2") (pintype "bidirectional"))
      (node (ref "FB1") (pin "1") (pinfunction "1_1") (pintype "bidirectional"))
      (node (ref "H2") (pin "27") (pinfunction "27_27") (pintype "passive"))
      (node (ref "H2") (pin "28") (pinfunction "28_28") (pintype "passive"))
      (node (ref "IC10") (pin "8") (pinfunction "VCC_8") (pintype "bidirectional"))
      (node (ref "IC7") (pin "104") (pinfunction "NVCC_GPIO_5_104") (pintype "bidirectional"))
      (node (ref "IC7") (pin "11") (pinfunction "NVCC_GPIO_1_11") (pintype "bidirectional"))
      (node (ref "IC7") (pin "112") (pinfunction "NVCC_GPIO_6_112") (pintype "bidirectional"))
      (node (ref "IC7") (pin "144") (pinfunction "NVCC_GPIO_7_144") (pintype "bidirectional"))
      (node (ref "IC7") (pin "20") (pinfunction "NVCC_GPIO_2_20") (pintype "bidirectional"))
      (node (ref "IC7") (pin "29") (pinfunction "NVCC_GPIO_3_29") (pintype "bidirectional"))
      (node (ref "IC7") (pin "34") (pinfunction "DCDC_IN_34") (pintype "bidirectional"))
      (node (ref "IC7") (pin "38") (pinfunction "DCDC_IN_Q_38") (pintype "bidirectional"))
      (node (ref "IC7") (pin "44") (pinfunction "NVCC_SD0_44") (pintype "bidirectional"))
      (node (ref "IC7") (pin "69") (pinfunction "VDD_HIGH_IN_69") (pintype "bidirectional"))
      (node (ref "IC7") (pin "73") (pinfunction "VDDA_ADC_3P3_73") (pintype "bidirectional"))
      (node (ref "IC7") (pin "77") (pinfunction "NVCC_GPIO_4_77") (pintype "bidirectional"))
      (node (ref "IC8") (pin "1") (pinfunction "EN_1") (pintype "bidirectional"))
      (node (ref "IC8") (pin "4") (pinfunction "VIN_4") (pintype "bidirectional"))
      (node (ref "J2") (pin "2") (pinfunction "2_2") (pintype "bidirectional"))
      (node (ref "R1") (pin "1") (pinfunction "1_1") (pintype "passive"))
      (node (ref "R11") (pin "2") (pinfunction "2_2") (pintype "passive"))
      (node (ref "R27") (pin "1") (pinfunction "1_1") (pintype "passive"))
      (node (ref "R3") (pin "1") (pinfunction "1_1") (pintype "passive"))
      (node (ref "R3") (pin "2") (pinfunction "2_2") (pintype "passive"))
      (node (ref "R4") (pin "1") (pinfunction "1_1") (pintype "passive"))
      (node (ref "R4") (pin "2") (pinfunction "2_2") (pintype "passive"))
      (node (ref "R5") (pin "1") (pinfunction "1_1") (pintype "passive"))
      (node (ref "R59") (pin "2") (pinfunction "2_2") (pintype "passive"))
      (node (ref "R6") (pin "1") (pinfunction "1_1") (pintype "passive"))
      (node (ref "R60") (pin "1") (pinfunction "1_1") (pintype "passive"))
      (node (ref "R60") (pin "2") (pinfunction "2_2") (pintype "passive"))
      (node (ref "R61") (pin "1") (pinfunction "1_1") (pintype "passive"))
      (node (ref "R61") (pin "2") (pinfunction "2_2") (pintype "passive"))
      (node (ref "R62") (pin "1") (pinfunction "1_1") (pintype "passive"))
      (node (ref "R62") (pin "2") (pinfunction "2_2") (pintype "passive"))
      (node (ref "R9") (pin "1") (pinfunction "1_1") (pintype "passive"))
    )
    (net (code "2") (name "/5V_USB") (class "Default")
      (node (ref "H2") (pin "52") (pinfunction "52_52") (pintype "passive"))
      (node (ref "PS1") (pin "1") (pinfunction "1_1") (pintype "bidirectional"))
    )
    (net (code "3") (name "/5V_USB_OTG") (class "Default")
      (node (ref "C3") (pin "2") (pinfunction "2_2") (pintype "passive"))
      (node (ref "IC7") (pin "59") (pinfunction "USB_OTG1_VBUS_59") (pintype "bidirectional"))
    )
    (net (code "4") (name "/ANT_BURN_WIRE1") (class "Default")
      (node (ref "H1") (pin "23") (pinfunction "23_23") (pintype "passive"))
      (node (ref "IC7") (pin "83") (pinfunction "GPIO_AD_B1_07_83") (pintype "bidirectional"))
    )
    (net (code "5") (name "/ANT_BURN_WIRE2") (class "Default")
      (node (ref "H1") (pin "25") (pinfunction "25_25") (pintype "passive"))
      (node (ref "IC7") (pin "78") (pinfunction "GPIO_AD_B1_12_78") (pintype "bidirectional"))
    )
    (net (code "6") (name "/CHASSIS") (class "Default")
      (node (ref "R64") (pin "2") (pinfunction "2_2") (pintype "passive"))
      (node (ref "R65") (pin "2") (pinfunction "2_2") (pintype "passive"))
      (node (ref "R66") (pin "2") (pinfunction "2_2") (pintype "passive"))
      (node (ref "R67") (pin "2") (pinfunction "2_2") (pintype "passive"))
    )
    (net (code "7") (name "/DCDC_OUT") (class "Default")
      (node (ref "C25") (pin "2") (pinfunction "2_2") (pintype "passive"))
      (node (ref "C26") (pin "2") (pinfunction "2_2") (pintype "passive"))
      (node (ref "C27") (pin "2") (pinfunction "2_2") (pintype "passive"))
      (node (ref "C28") (pin "2") (pinfunction "2_2") (pintype "passive"))
      (node (ref "C29") (pin "2") (pinfunction "2_2") (pintype "passive"))
      (node (ref "C30") (pin "2") (pinfunction "2_2") (pintype "passive"))
      (node (ref "C31") (pin "2") (pinfunction "2_2") (pintype "passive"))
      (node (ref "C33") (pin "2") (pinfunction "2_2") (pintype "passive"))
      (node (ref "C34") (pin "2") (pinfunction "2_2") (pintype "passive"))
      (node (ref "C35") (pin "2") (pinfunction "2_2") (pintype "passive"))
      (node (ref "C45") (pin "2") (pinfunction "2_2") (pintype "passive"))
      (node (ref "C46") (pin "2") (pinfunction "2_2") (pintype "passive"))
      (node (ref "IC7") (pin "102") (pinfunction "VDD_SOC_IN_5_102") (pintype "bidirectional"))
      (node (ref "IC7") (pin "114") (pinfunction "VDD_SOC_IN_6_114") (pintype "bidirectional"))
      (node (ref "IC7") (pin "134") (pinfunction "VDD_SOC_IN_7_134") (pintype "bidirectional"))
      (node (ref "IC7") (pin "31") (pinfunction "VDD_SOC_IN_2_31") (pintype "bidirectional"))
      (node (ref "IC7") (pin "39") (pinfunction "VDD_SOC_IN_3_39") (pintype "bidirectional"))
      (node (ref "IC7") (pin "5") (pinfunction "VDD_SOC_IN_1_5") (pintype "bidirectional"))
      (node (ref "IC7") (pin "86") (pinfunction "VDD_SOC_IN_4_86") (pintype "bidirectional"))
      (node (ref "L2") (pin "1") (pinfunction "1_1") (pintype "bidirectional"))
    )
    (net (code "8") (name "/DTR") (class "Default")
      (node (ref "H1") (pin "5") (pinfunction "5_5") (pintype "passive"))
      (node (ref "IC7") (pin "26") (pinfunction "GPIO_SD_B1_05_26") (pintype "bidirectional"))
    )
    (net (code "9") (name "/FLEXSPI_CLK") (class "Default")
      (node (ref "IC10") (pin "6") (pinfunction "SCK_6") (pintype "bidirectional"))
      (node (ref "IC7") (pin "24") (pinfunction "GPIO_SD_B1_07_24") (pintype "bidirectional"))
    )
    (net (code "10") (name "/FLEXSPI_D0_A") (class "Default")
      (node (ref "IC10") (pin "5") (pinfunction "SI_(IO0)_5") (pintype "bidirectional"))
      (node (ref "IC7") (pin "23") (pinfunction "GPIO_SD_B1_08_23") (pintype "bidirectional"))
    )
    (net (code "11") (name "/FLEXSPI_D1_A") (class "Default")
      (node (ref "IC10") (pin "2") (pinfunction "SO_(IO1)_2") (pintype "bidirectional"))
      (node (ref "IC7") (pin "21") (pinfunction "GPIO_SD_B1_10_21") (pintype "bidirectional"))
    )
    (net (code "12") (name "/FLEXSPI_D2_A") (class "Default")
      (node (ref "IC10") (pin "3") (pinfunction "WP#_(IO2)_3") (pintype "bidirectional"))
      (node (ref "IC7") (pin "22") (pinfunction "GPIO_SD_B1_09_22") (pintype "bidirectional"))
    )
    (net (code "13") (name "/FLEXSPI_D3_A") (class "Default")
      (node (ref "IC10") (pin "7") (pinfunction "HOLD#_(IO3)_7") (pintype "bidirectional"))
      (node (ref "IC7") (pin "25") (pinfunction "GPIO_SD_B1_06_25") (pintype "bidirectional"))
    )
    (net (code "14") (name "/FLEXSPI_SS0") (class "Default")
      (node (ref "IC10") (pin "1") (pinfunction "CE#_1") (pintype "bidirectional"))
      (node (ref "IC7") (pin "19") (pinfunction "GPIO_SD_B1_11_19") (pintype "bidirectional"))
      (node (ref "R1") (pin "2") (pinfunction "2_2") (pintype "passive"))
    )
    (net (code "15") (name "/GPANAIO") (class "Default")
      (node (ref "IC7") (pin "71") (pinfunction "GPANAIO_71") (pintype "bidirectional"))
      (node (ref "TP7") (pin "TP") (pinfunction "TP_TP") (pintype "input"))
    )
    (net (code "16") (name "/I2C1_SCL") (class "Default")
      (node (ref "H1") (pin "44") (pinfunction "44_44") (pintype "passive"))
      (node (ref "IC7") (pin "75") (pinfunction "GPIO_AD_B1_14_75") (pintype "bidirectional"))
    )
    (net (code "17") (name "/I2C1_SDA") (class "Default")
      (node (ref "H1") (pin "42") (pinfunction "42_42") (pintype "passive"))
      (node (ref "IC7") (pin "74") (pinfunction "GPIO_AD_B1_15_74") (pintype "bidirectional"))
    )
    (net (code "18") (name "/I2C2_SCL") (class "Default")
      (node (ref "H1") (pin "37") (pinfunction "37_37") (pintype "passive"))
      (node (ref "IC7") (pin "82") (pinfunction "GPIO_AD_B1_08_82") (pintype "bidirectional"))
    )
    (net (code "19") (name "/I2C2_SDA") (class "Default")
      (node (ref "H1") (pin "35") (pinfunction "35_35") (pintype "passive"))
      (node (ref "IC7") (pin "81") (pinfunction "GPIO_AD_B1_09_81") (pintype "bidirectional"))
    )
    (net (code "20") (name "/I2C3_SCL") (class "Default")
      (node (ref "H1") (pin "51") (pinfunction "51_51") (pintype "passive"))
      (node (ref "IC7") (pin "100") (pinfunction "GPIO_AD_B0_08_100") (pintype "bidirectional"))
    )
    (net (code "21") (name "/I2C3_SDA") (class "Default")
      (node (ref "H1") (pin "49") (pinfunction "49_49") (pintype "passive"))
      (node (ref "IC7") (pin "99") (pinfunction "GPIO_AD_B0_09_99") (pintype "bidirectional"))
    )
    (net (code "22") (name "/JTAG_DACK") (class "Default")
      (node (ref "J2") (pin "17") (pinfunction "17_17") (pintype "bidirectional"))
      (node (ref "R26") (pin "1") (pinfunction "1_1") (pintype "passive"))
    )
    (net (code "23") (name "/JTAG_DE") (class "Default")
      (node (ref "J2") (pin "20") (pinfunction "20_20") (pintype "bidirectional"))
    )
    (net (code "24") (name "/JTAG_MOD") (class "Default")
      (node (ref "IC7") (pin "109") (pinfunction "GPIO_AD_B0_02_109") (pintype "bidirectional"))
      (node (ref "R2") (pin "2") (pinfunction "2_2") (pintype "passive"))
    )
    (net (code "25") (name "/JTAG_NSRST") (class "Default")
      (node (ref "D2") (pin "1") (pinfunction "K_1") (pintype "bidirectional"))
      (node (ref "J2") (pin "15") (pinfunction "15_15") (pintype "bidirectional"))
    )
    (net (code "26") (name "/JTAG_NTRST") (class "Default")
      (node (ref "D11") (pin "1") (pinfunction "CATHODE_1") (pintype "passive"))
      (node (ref "IC7") (pin "106") (pinfunction "GPIO_AD_B0_05_106") (pintype "bidirectional"))
      (node (ref "J2") (pin "3") (pinfunction "3_3") (pintype "bidirectional"))
    )
    (net (code "27") (name "/JTAG_RTCK") (class "Default")
      (node (ref "J2") (pin "11") (pinfunction "11_11") (pintype "bidirectional"))
    )
    (net (code "28") (name "/JTAG_TCK") (class "Default")
      (node (ref "IC7") (pin "110") (pinfunction "GPIO_AD_B0_01_110") (pintype "bidirectional"))
      (node (ref "J2") (pin "9") (pinfunction "9_9") (pintype "bidirectional"))
    )
    (net (code "29") (name "/JTAG_TDI") (class "Default")
      (node (ref "IC7") (pin "108") (pinfunction "GPIO_AD_B0_03_108") (pintype "bidirectional"))
      (node (ref "J2") (pin "5") (pinfunction "5_5") (pintype "bidirectional"))
    )
    (net (code "30") (name "/JTAG_TDO") (class "Default")
      (node (ref "IC7") (pin "107") (pinfunction "GPIO_AD_B0_04_107") (pintype "bidirectional"))
      (node (ref "J2") (pin "13") (pinfunction "13_13") (pintype "bidirectional"))
    )
    (net (code "31") (name "/JTAG_TMS") (class "Default")
      (node (ref "IC7") (pin "111") (pinfunction "GPIO_AD_B0_00_111") (pintype "bidirectional"))
      (node (ref "J2") (pin "7") (pinfunction "7_7") (pintype "bidirectional"))
    )
    (net (code "32") (name "/NVCC_PLL") (class "Default")
      (node (ref "C22") (pin "2") (pinfunction "2_2") (pintype "passive"))
      (node (ref "IC7") (pin "72") (pinfunction "NVCC_PLL_72") (pintype "bidirectional"))
    )
    (net (code "33") (name "/PMIC_STBY_REQ") (class "Default")
      (node (ref "IC7") (pin "54") (pinfunction "PMIC_STBY_REQ_54") (pintype "bidirectional"))
      (node (ref "TP6") (pin "TP") (pinfunction "TP_TP") (pintype "input"))
    )
    (net (code "34") (name "/POR_B") (class "Default")
      (node (ref "C36") (pin "2") (pinfunction "2_2") (pintype "passive"))
      (node (ref "D2") (pin "2") (pinfunction "A_2") (pintype "bidirectional"))
      (node (ref "D4") (pin "1") (pinfunction "K_1") (pintype "bidirectional"))
      (node (ref "IC1") (pin "2") (pinfunction "~{RESET}_2") (pintype "bidirectional"))
      (node (ref "IC7") (pin "50") (pinfunction "POR_B_50") (pintype "bidirectional"))
      (node (ref "R8") (pin "1") (pinfunction "1_1") (pintype "passive"))
      (node (ref "R8") (pin "2") (pinfunction "2_2") (pintype "passive"))
    )
    (net (code "35") (name "/RTC_XTALI") (class "Default")
      (node (ref "C41") (pin "2") (pinfunction "2_2") (pintype "passive"))
      (node (ref "IC7") (pin "57") (pinfunction "RTC_XTALI_57") (pintype "bidirectional"))
      (node (ref "Y2") (pin "1") (pinfunction "IN/OUT_1") (pintype "bidirectional"))
    )
    (net (code "36") (name "/RTC_XTALO") (class "Default")
      (node (ref "C42") (pin "2") (pinfunction "2_2") (pintype "passive"))
      (node (ref "IC7") (pin "58") (pinfunction "RTC_XTALO_58") (pintype "bidirectional"))
      (node (ref "Y2") (pin "2") (pinfunction "OUT/IN_2") (pintype "bidirectional"))
    )
    (net (code "37") (name "/SD1_CLK") (class "Default")
      (node (ref "IC7") (pin "45") (pinfunction "GPIO_SD_B0_03_45") (pintype "bidirectional"))
      (node (ref "J1") (pin "5") (pinfunction "CLK_5") (pintype "input"))
      (node (ref "R56") (pin "1") (pinfunction "1_1") (pintype "passive"))
      (node (ref "R56") (pin "2") (pinfunction "2_2") (pintype "passive"))
    )
    (net (code "38") (name "/SD1_CMD") (class "Default")
      (node (ref "IC7") (pin "46") (pinfunction "GPIO_SD_B0_02_46") (pintype "bidirectional"))
      (node (ref "J1") (pin "3") (pinfunction "CMD_3") (pintype "bidirectional"))
      (node (ref "R5") (pin "2") (pinfunction "2_2") (pintype "passive"))
      (node (ref "R55") (pin "1") (pinfunction "1_1") (pintype "passive"))
      (node (ref "R55") (pin "2") (pinfunction "2_2") (pintype "passive"))
    )
    (net (code "39") (name "/SD1_D0") (class "Default")
      (node (ref "IC7") (pin "43") (pinfunction "GPIO_SD_B0_04_43") (pintype "bidirectional"))
      (node (ref "J1") (pin "7") (pinfunction "DAT0_7") (pintype "bidirectional"))
      (node (ref "R57") (pin "1") (pinfunction "1_1") (pintype "passive"))
      (node (ref "R57") (pin "2") (pinfunction "2_2") (pintype "passive"))
      (node (ref "R6") (pin "2") (pinfunction "2_2") (pintype "passive"))
    )
    (net (code "40") (name "/SD1_D1") (class "Default")
      (node (ref "IC7") (pin "42") (pinfunction "GPIO_SD_B0_05_42") (pintype "bidirectional"))
      (node (ref "J1") (pin "8") (pinfunction "DAT1_8") (pintype "bidirectional"))
      (node (ref "R58") (pin "1") (pinfunction "1_1") (pintype "passive"))
      (node (ref "R58") (pin "2") (pinfunction "2_2") (pintype "passive"))
    )
    (net (code "41") (name "/SD1_D2") (class "Default")
      (node (ref "IC7") (pin "48") (pinfunction "GPIO_SD_B0_00_48") (pintype "bidirectional"))
      (node (ref "J1") (pin "1") (pinfunction "DATA2_1") (pintype "bidirectional"))
      (node (ref "R53") (pin "1") (pinfunction "1_1") (pintype "passive"))
      (node (ref "R53") (pin "2") (pinfunction "2_2") (pintype "passive"))
    )
    (net (code "42") (name "/SD1_D3") (class "Default")
      (node (ref "IC7") (pin "47") (pinfunction "GPIO_SD_B0_01_47") (pintype "bidirectional"))
      (node (ref "J1") (pin "2") (pinfunction "CD/DAT3_2") (pintype "bidirectional"))
      (node (ref "R54") (pin "1") (pinfunction "1_1") (pintype "passive"))
      (node (ref "R54") (pin "2") (pinfunction "2_2") (pintype "passive"))
    )
    (net (code "43") (name "/SDRAM_3V3") (class "Default")
      (node (ref "C10") (pin "1") (pinfunction "1_1") (pintype "passive"))
      (node (ref "C11") (pin "1") (pinfunction "1_1") (pintype "passive"))
      (node (ref "C12") (pin "1") (pinfunction "1_1") (pintype "passive"))
      (node (ref "C13") (pin "1") (pinfunction "1_1") (pintype "passive"))
      (node (ref "C6") (pin "1") (pinfunction "1_1") (pintype "passive"))
      (node (ref "C7") (pin "1") (pinfunction "1_1") (pintype "passive"))
      (node (ref "C8") (pin "1") (pinfunction "1_1") (pintype "passive"))
      (node (ref "C9") (pin "1") (pinfunction "1_1") (pintype "passive"))
      (node (ref "FB1") (pin "2") (pinfunction "2_2") (pintype "bidirectional"))
      (node (ref "IC9") (pin "1") (pinfunction "VDD_1_1") (pintype "bidirectional"))
      (node (ref "IC9") (pin "14") (pinfunction "VDD_2_14") (pintype "bidirectional"))
      (node (ref "IC9") (pin "27") (pinfunction "VDD_3_27") (pintype "bidirectional"))
      (node (ref "IC9") (pin "3") (pinfunction "VDDQ_1_3") (pintype "bidirectional"))
      (node (ref "IC9") (pin "43") (pinfunction "VDDQ_3_43") (pintype "bidirectional"))
      (node (ref "IC9") (pin "49") (pinfunction "VDDQ_4_49") (pintype "bidirectional"))
      (node (ref "IC9") (pin "9") (pinfunction "VDDQ_2_9") (pintype "bidirectional"))
    )
    (net (code "44") (name "/SD_CD_SW") (class "Default")
      (node (ref "IC7") (pin "41") (pinfunction "GPIO_SD_B0_06_41") (pintype "bidirectional"))
      (node (ref "J1") (pin "9") (pinfunction "9_9") (pintype "bidirectional"))
      (node (ref "R59") (pin "1") (pinfunction "1_1") (pintype "passive"))
    )
    (net (code "45") (name "/SD_PWREN") (class "Default")
      (node (ref "D3") (pin "1") (pinfunction "K_1") (pintype "bidirectional"))
      (node (ref "IC7") (pin "27") (pinfunction "GPIO_SD_B1_04_27") (pintype "bidirectional"))
      (node (ref "R7") (pin "1") (pinfunction "1_1") (pintype "passive"))
      (node (ref "R7") (pin "2") (pinfunction "2_2") (pintype "passive"))
    )
    (net (code "46") (name "/SEMC_A0") (class "Default")
      (node (ref "IC7") (pin "142") (pinfunction "GPIO_EMC_16_142") (pintype "bidirectional"))
      (node (ref "IC9") (pin "23") (pinfunction "A0_23") (pintype "bidirectional"))
      (node (ref "R49") (pin "1") (pinfunction "1_1") (pintype "passive"))
      (node (ref "R49") (pin "2") (pinfunction "2_2") (pintype "passive"))
    )
    (net (code "47") (name "/SEMC_A1") (class "Default")
      (node (ref "IC7") (pin "141") (pinfunction "GPIO_EMC_17_141") (pintype "bidirectional"))
      (node (ref "IC9") (pin "24") (pinfunction "A1_24") (pintype "bidirectional"))
      (node (ref "R50") (pin "1") (pinfunction "1_1") (pintype "passive"))
      (node (ref "R50") (pin "2") (pinfunction "2_2") (pintype "passive"))
    )
    (net (code "48") (name "/SEMC_A2") (class "Default")
      (node (ref "IC7") (pin "140") (pinfunction "GPIO_EMC_18_140") (pintype "bidirectional"))
      (node (ref "IC9") (pin "25") (pinfunction "A2_25") (pintype "bidirectional"))
      (node (ref "R51") (pin "1") (pinfunction "1_1") (pintype "passive"))
      (node (ref "R51") (pin "2") (pinfunction "2_2") (pintype "passive"))
    )
    (net (code "49") (name "/SEMC_A3") (class "Default")
      (node (ref "IC7") (pin "139") (pinfunction "GPIO_EMC_19_139") (pintype "bidirectional"))
      (node (ref "IC9") (pin "26") (pinfunction "A3_26") (pintype "bidirectional"))
      (node (ref "R52") (pin "1") (pinfunction "1_1") (pintype "passive"))
      (node (ref "R52") (pin "2") (pinfunction "2_2") (pintype "passive"))
    )
    (net (code "50") (name "/SEMC_A4") (class "Default")
      (node (ref "IC7") (pin "138") (pinfunction "GPIO_EMC_20_138") (pintype "bidirectional"))
      (node (ref "IC9") (pin "29") (pinfunction "A4_29") (pintype "bidirectional"))
      (node (ref "R32") (pin "1") (pinfunction "1_1") (pintype "passive"))
      (node (ref "R32") (pin "2") (pinfunction "2_2") (pintype "passive"))
    )
    (net (code "51") (name "/SEMC_A5") (class "Default")
      (node (ref "IC7") (pin "137") (pinfunction "GPIO_EMC_21_137") (pintype "bidirectional"))
      (node (ref "IC9") (pin "30") (pinfunction "A5_30") (pintype "bidirectional"))
      (node (ref "R31") (pin "1") (pinfunction "1_1") (pintype "passive"))
      (node (ref "R31") (pin "2") (pinfunction "2_2") (pintype "passive"))
    )
    (net (code "52") (name "/SEMC_A6") (class "Default")
      (node (ref "IC7") (pin "136") (pinfunction "GPIO_EMC_22_136") (pintype "bidirectional"))
      (node (ref "IC9") (pin "31") (pinfunction "A6_31") (pintype "bidirectional"))
      (node (ref "R30") (pin "1") (pinfunction "1_1") (pintype "passive"))
      (node (ref "R30") (pin "2") (pinfunction "2_2") (pintype "passive"))
    )
    (net (code "53") (name "/SEMC_A7") (class "Default")
      (node (ref "IC7") (pin "133") (pinfunction "GPIO_EMC_23_133") (pintype "bidirectional"))
      (node (ref "IC9") (pin "32") (pinfunction "A7_32") (pintype "bidirectional"))
      (node (ref "R29") (pin "1") (pinfunction "1_1") (pintype "passive"))
      (node (ref "R29") (pin "2") (pinfunction "2_2") (pintype "passive"))
    )
    (net (code "54") (name "/SEMC_A8") (class "Default")
      (node (ref "IC7") (pin "132") (pinfunction "GPIO_EMC_24_132") (pintype "bidirectional"))
      (node (ref "IC9") (pin "33") (pinfunction "A8_33") (pintype "bidirectional"))
      (node (ref "R28") (pin "1") (pinfunction "1_1") (pintype "passive"))
      (node (ref "R28") (pin "2") (pinfunction "2_2") (pintype "passive"))
    )
    (net (code "55") (name "/SEMC_A9") (class "Default")
      (node (ref "IC7") (pin "131") (pinfunction "GPIO_EMC_25_131") (pintype "bidirectional"))
      (node (ref "IC9") (pin "34") (pinfunction "A9_34") (pintype "bidirectional"))
      (node (ref "R25") (pin "1") (pinfunction "1_1") (pintype "passive"))
      (node (ref "R25") (pin "2") (pinfunction "2_2") (pintype "passive"))
    )
    (net (code "56") (name "/SEMC_A10") (class "Default")
      (node (ref "IC7") (pin "143") (pinfunction "GPIO_EMC_15_143") (pintype "bidirectional"))
      (node (ref "IC9") (pin "22") (pinfunction "A10_22") (pintype "bidirectional"))
      (node (ref "R48") (pin "1") (pinfunction "1_1") (pintype "passive"))
      (node (ref "R48") (pin "2") (pinfunction "2_2") (pintype "passive"))
    )
    (net (code "57") (name "/SEMC_A11") (class "Default")
      (node (ref "IC7") (pin "130") (pinfunction "GPIO_EMC_26_130") (pintype "bidirectional"))
      (node (ref "IC9") (pin "35") (pinfunction "A11_35") (pintype "bidirectional"))
      (node (ref "R24") (pin "1") (pinfunction "1_1") (pintype "passive"))
      (node (ref "R24") (pin "2") (pinfunction "2_2") (pintype "passive"))
    )
    (net (code "58") (name "/SEMC_A12") (class "Default")
      (node (ref "IC7") (pin "129") (pinfunction "GPIO_EMC_27_129") (pintype "bidirectional"))
      (node (ref "IC9") (pin "36") (pinfunction "A12_36") (pintype "bidirectional"))
      (node (ref "R23") (pin "1") (pinfunction "1_1") (pintype "passive"))
      (node (ref "R23") (pin "2") (pinfunction "2_2") (pintype "passive"))
    )
    (net (code "59") (name "/SEMC_BA0") (class "Default")
      (node (ref "IC7") (pin "2") (pinfunction "GPIO_EMC_13_2") (pintype "bidirectional"))
      (node (ref "IC9") (pin "20") (pinfunction "BA0_20") (pintype "bidirectional"))
      (node (ref "R46") (pin "1") (pinfunction "1_1") (pintype "passive"))
      (node (ref "R46") (pin "2") (pinfunction "2_2") (pintype "passive"))
    )
    (net (code "60") (name "/SEMC_BA1") (class "Default")
      (node (ref "IC7") (pin "1") (pinfunction "GPIO_EMC_14_1") (pintype "bidirectional"))
      (node (ref "IC9") (pin "21") (pinfunction "BA1_21") (pintype "bidirectional"))
      (node (ref "R47") (pin "1") (pinfunction "1_1") (pintype "passive"))
      (node (ref "R47") (pin "2") (pinfunction "2_2") (pintype "passive"))
    )
    (net (code "61") (name "/SEMC_CAS") (class "Default")
      (node (ref "IC7") (pin "7") (pinfunction "GPIO_EMC_10_7") (pintype "bidirectional"))
      (node (ref "IC9") (pin "17") (pinfunction "~{CAS}_17") (pintype "bidirectional"))
      (node (ref "R43") (pin "1") (pinfunction "1_1") (pintype "passive"))
      (node (ref "R43") (pin "2") (pinfunction "2_2") (pintype "passive"))
    )
    (net (code "62") (name "/SEMC_CKE") (class "Default")
      (node (ref "IC7") (pin "127") (pinfunction "GPIO_EMC_29_127") (pintype "bidirectional"))
      (node (ref "IC9") (pin "37") (pinfunction "CKE_37") (pintype "bidirectional"))
      (node (ref "R22") (pin "1") (pinfunction "1_1") (pintype "passive"))
      (node (ref "R22") (pin "2") (pinfunction "2_2") (pintype "passive"))
    )
    (net (code "63") (name "/SEMC_CLK") (class "Default")
      (node (ref "IC7") (pin "126") (pinfunction "GPIO_EMC_30_126") (pintype "bidirectional"))
      (node (ref "IC9") (pin "38") (pinfunction "CLK_38") (pintype "bidirectional"))
      (node (ref "R21") (pin "1") (pinfunction "1_1") (pintype "passive"))
      (node (ref "R21") (pin "2") (pinfunction "2_2") (pintype "passive"))
    )
    (net (code "64") (name "/SEMC_CS0") (class "Default")
      (node (ref "IC7") (pin "3") (pinfunction "GPIO_EMC_12_3") (pintype "bidirectional"))
      (node (ref "IC9") (pin "19") (pinfunction "~{CS}_19") (pintype "bidirectional"))
      (node (ref "R45") (pin "1") (pinfunction "1_1") (pintype "passive"))
      (node (ref "R45") (pin "2") (pinfunction "2_2") (pintype "passive"))
    )
    (net (code "65") (name "/SEMC_D0") (class "Default")
      (node (ref "IC7") (pin "18") (pinfunction "GPIO_EMC_00_18") (pintype "bidirectional"))
      (node (ref "IC9") (pin "2") (pinfunction "DQ0_2") (pintype "bidirectional"))
      (node (ref "R33") (pin "1") (pinfunction "1_1") (pintype "passive"))
      (node (ref "R33") (pin "2") (pinfunction "2_2") (pintype "passive"))
    )
    (net (code "66") (name "/SEMC_D1") (class "Default")
      (node (ref "IC7") (pin "17") (pinfunction "GPIO_EMC_01_17") (pintype "bidirectional"))
      (node (ref "IC9") (pin "4") (pinfunction "NC_1_4") (pintype "bidirectional"))
      (node (ref "R34") (pin "1") (pinfunction "1_1") (pintype "passive"))
      (node (ref "R34") (pin "2") (pinfunction "2_2") (pintype "passive"))
    )
    (net (code "67") (name "/SEMC_D2") (class "Default")
      (node (ref "IC7") (pin "16") (pinfunction "GPIO_EMC_02_16") (pintype "bidirectional"))
      (node (ref "IC9") (pin "5") (pinfunction "DQ1_5") (pintype "bidirectional"))
      (node (ref "R35") (pin "1") (pinfunction "1_1") (pintype "passive"))
      (node (ref "R35") (pin "2") (pinfunction "2_2") (pintype "passive"))
    )
    (net (code "68") (name "/SEMC_D3") (class "Default")
      (node (ref "IC7") (pin "15") (pinfunction "GPIO_EMC_03_15") (pintype "bidirectional"))
      (node (ref "IC9") (pin "7") (pinfunction "NC_2_7") (pintype "bidirectional"))
      (node (ref "R36") (pin "1") (pinfunction "1_1") (pintype "passive"))
      (node (ref "R36") (pin "2") (pinfunction "2_2") (pintype "passive"))
    )
    (net (code "69") (name "/SEMC_D4") (class "Default")
      (node (ref "IC7") (pin "14") (pinfunction "GPIO_EMC_04_14") (pintype "bidirectional"))
      (node (ref "IC9") (pin "8") (pinfunction "DQ2_8") (pintype "bidirectional"))
      (node (ref "R37") (pin "1") (pinfunction "1_1") (pintype "passive"))
      (node (ref "R37") (pin "2") (pinfunction "2_2") (pintype "passive"))
    )
    (net (code "70") (name "/SEMC_D5") (class "Default")
      (node (ref "IC7") (pin "13") (pinfunction "GPIO_EMC_05_13") (pintype "bidirectional"))
      (node (ref "IC9") (pin "10") (pinfunction "NC_3_10") (pintype "bidirectional"))
      (node (ref "R38") (pin "1") (pinfunction "1_1") (pintype "passive"))
      (node (ref "R38") (pin "2") (pinfunction "2_2") (pintype "passive"))
    )
    (net (code "71") (name "/SEMC_D6") (class "Default")
      (node (ref "IC7") (pin "12") (pinfunction "GPIO_EMC_06_12") (pintype "bidirectional"))
      (node (ref "IC9") (pin "11") (pinfunction "DQ3_11") (pintype "bidirectional"))
      (node (ref "R39") (pin "1") (pinfunction "1_1") (pintype "passive"))
      (node (ref "R39") (pin "2") (pinfunction "2_2") (pintype "passive"))
    )
    (net (code "72") (name "/SEMC_D7") (class "Default")
      (node (ref "IC7") (pin "10") (pinfunction "GPIO_EMC_07_10") (pintype "bidirectional"))
      (node (ref "IC9") (pin "13") (pinfunction "NC_4_13") (pintype "bidirectional"))
      (node (ref "R40") (pin "1") (pinfunction "1_1") (pintype "passive"))
      (node (ref "R40") (pin "2") (pinfunction "2_2") (pintype "passive"))
    )
    (net (code "73") (name "/SEMC_D8") (class "Default")
      (node (ref "IC7") (pin "124") (pinfunction "GPIO_EMC_32_124") (pintype "bidirectional"))
      (node (ref "IC9") (pin "42") (pinfunction "NC_7_42") (pintype "bidirectional"))
      (node (ref "R19") (pin "1") (pinfunction "1_1") (pintype "passive"))
      (node (ref "R19") (pin "2") (pinfunction "2_2") (pintype "passive"))
    )
    (net (code "74") (name "/SEMC_D9") (class "Default")
      (node (ref "IC7") (pin "123") (pinfunction "GPIO_EMC_33_123") (pintype "bidirectional"))
      (node (ref "IC9") (pin "44") (pinfunction "DQ4_44") (pintype "bidirectional"))
      (node (ref "R18") (pin "1") (pinfunction "1_1") (pintype "passive"))
      (node (ref "R18") (pin "2") (pinfunction "2_2") (pintype "passive"))
    )
    (net (code "75") (name "/SEMC_D10") (class "Default")
      (node (ref "IC7") (pin "122") (pinfunction "GPIO_EMC_34_122") (pintype "bidirectional"))
      (node (ref "IC9") (pin "45") (pinfunction "NC_8_45") (pintype "bidirectional"))
      (node (ref "R17") (pin "1") (pinfunction "1_1") (pintype "passive"))
      (node (ref "R17") (pin "2") (pinfunction "2_2") (pintype "passive"))
    )
    (net (code "76") (name "/SEMC_D11") (class "Default")
      (node (ref "IC7") (pin "121") (pinfunction "GPIO_EMC_35_121") (pintype "bidirectional"))
      (node (ref "IC9") (pin "47") (pinfunction "DQ5_47") (pintype "bidirectional"))
      (node (ref "R16") (pin "1") (pinfunction "1_1") (pintype "passive"))
      (node (ref "R16") (pin "2") (pinfunction "2_2") (pintype "passive"))
    )
    (net (code "77") (name "/SEMC_D12") (class "Default")
      (node (ref "IC7") (pin "120") (pinfunction "GPIO_EMC_36_120") (pintype "bidirectional"))
      (node (ref "IC9") (pin "48") (pinfunction "NC_9_48") (pintype "bidirectional"))
      (node (ref "R15") (pin "1") (pinfunction "1_1") (pintype "passive"))
      (node (ref "R15") (pin "2") (pinfunction "2_2") (pintype "passive"))
    )
    (net (code "78") (name "/SEMC_D13") (class "Default")
      (node (ref "IC7") (pin "119") (pinfunction "GPIO_EMC_37_119") (pintype "bidirectional"))
      (node (ref "IC9") (pin "50") (pinfunction "DQ6_50") (pintype "bidirectional"))
      (node (ref "R14") (pin "1") (pinfunction "1_1") (pintype "passive"))
      (node (ref "R14") (pin "2") (pinfunction "2_2") (pintype "passive"))
    )
    (net (code "79") (name "/SEMC_D14") (class "Default")
      (node (ref "IC7") (pin "118") (pinfunction "GPIO_EMC_38_118") (pintype "bidirectional"))
      (node (ref "IC9") (pin "51") (pinfunction "NC_10_51") (pintype "bidirectional"))
      (node (ref "R13") (pin "1") (pinfunction "1_1") (pintype "passive"))
      (node (ref "R13") (pin "2") (pinfunction "2_2") (pintype "passive"))
    )
    (net (code "80") (name "/SEMC_D15") (class "Default")
      (node (ref "IC7") (pin "117") (pinfunction "GPIO_EMC_39_117") (pintype "bidirectional"))
      (node (ref "IC9") (pin "53") (pinfunction "DQ7_53") (pintype "bidirectional"))
      (node (ref "R12") (pin "1") (pinfunction "1_1") (pintype "passive"))
      (node (ref "R12") (pin "2") (pinfunction "2_2") (pintype "passive"))
    )
    (net (code "81") (name "/SEMC_DM0") (class "Default")
      (node (ref "IC7") (pin "9") (pinfunction "GPIO_EMC_08_9") (pintype "bidirectional"))
      (node (ref "IC9") (pin "15") (pinfunction "NC_5_15") (pintype "bidirectional"))
      (node (ref "R41") (pin "1") (pinfunction "1_1") (pintype "passive"))
      (node (ref "R41") (pin "2") (pinfunction "2_2") (pintype "passive"))
    )
    (net (code "82") (name "/SEMC_DM1") (class "Default")
      (node (ref "IC7") (pin "125") (pinfunction "GPIO_EMC_31_125") (pintype "bidirectional"))
      (node (ref "IC9") (pin "39") (pinfunction "DQM_39") (pintype "bidirectional"))
      (node (ref "R20") (pin "1") (pinfunction "1_1") (pintype "passive"))
      (node (ref "R20") (pin "2") (pinfunction "2_2") (pintype "passive"))
    )
    (net (code "83") (name "/SEMC_RAS") (class "Default")
      (node (ref "IC7") (pin "4") (pinfunction "GPIO_EMC_11_4") (pintype "bidirectional"))
      (node (ref "IC9") (pin "18") (pinfunction "~{RAS}_18") (pintype "bidirectional"))
      (node (ref "R44") (pin "1") (pinfunction "1_1") (pintype "passive"))
      (node (ref "R44") (pin "2") (pinfunction "2_2") (pintype "passive"))
    )
    (net (code "84") (name "/SEMC_WE") (class "Default")
      (node (ref "IC7") (pin "8") (pinfunction "GPIO_EMC_09_8") (pintype "bidirectional"))
      (node (ref "IC9") (pin "16") (pinfunction "~{WE}_16") (pintype "bidirectional"))
      (node (ref "R42") (pin "1") (pinfunction "1_1") (pintype "passive"))
      (node (ref "R42") (pin "2") (pinfunction "2_2") (pintype "passive"))
    )
    (net (code "85") (name "/SPI1_EN0") (class "Default")
      (node (ref "H1") (pin "9") (pinfunction "9_9") (pintype "passive"))
      (node (ref "IC7") (pin "92") (pinfunction "GPIO_AD_B1_00_92") (pintype "bidirectional"))
    )
    (net (code "86") (name "/SPI1_EN1") (class "Default")
      (node (ref "H1") (pin "10") (pinfunction "10_10") (pintype "passive"))
      (node (ref "IC7") (pin "91") (pinfunction "GPIO_AD_B1_01_91") (pintype "bidirectional"))
    )
    (net (code "87") (name "/SPI1_EN2") (class "Default")
      (node (ref "H1") (pin "22") (pinfunction "22_22") (pintype "passive"))
      (node (ref "IC7") (pin "90") (pinfunction "GPIO_AD_B1_02_90") (pintype "bidirectional"))
    )
    (net (code "88") (name "/SPI1_EN3") (class "Default")
      (node (ref "H1") (pin "21") (pinfunction "21_21") (pintype "passive"))
      (node (ref "IC7") (pin "89") (pinfunction "GPIO_AD_B1_03_89") (pintype "bidirectional"))
    )
    (net (code "89") (name "/SPI1_MISO") (class "Default")
      (node (ref "H1") (pin "18") (pinfunction "18_18") (pintype "passive"))
      (node (ref "IC7") (pin "95") (pinfunction "GPIO_AD_B0_13_95") (pintype "bidirectional"))
    )
    (net (code "90") (name "/SPI1_MOSI") (class "Default")
      (node (ref "H1") (pin "16") (pinfunction "16_16") (pintype "passive"))
      (node (ref "IC7") (pin "96") (pinfunction "GPIO_AD_B0_12_96") (pintype "bidirectional"))
    )
    (net (code "91") (name "/SPI1_PCS0") (class "Default")
      (node (ref "H1") (pin "7") (pinfunction "7_7") (pintype "passive"))
      (node (ref "IC7") (pin "97") (pinfunction "GPIO_AD_B0_11_97") (pintype "bidirectional"))
    )
    (net (code "92") (name "/SPI1_PCS1") (class "Default")
      (node (ref "H1") (pin "8") (pinfunction "8_8") (pintype "passive"))
      (node (ref "IC7") (pin "88") (pinfunction "GPIO_AD_B1_04_88") (pintype "bidirectional"))
    )
    (net (code "93") (name "/SPI1_PCS2") (class "Default")
      (node (ref "H1") (pin "20") (pinfunction "20_20") (pintype "passive"))
      (node (ref "IC7") (pin "87") (pinfunction "GPIO_AD_B1_05_87") (pintype "bidirectional"))
    )
    (net (code "94") (name "/SPI1_PCS3") (class "Default")
      (node (ref "H1") (pin "19") (pinfunction "19_19") (pintype "passive"))
      (node (ref "IC7") (pin "84") (pinfunction "GPIO_AD_B1_06_84") (pintype "bidirectional"))
    )
    (net (code "95") (name "/SPI1_SCK") (class "Default")
      (node (ref "H1") (pin "12") (pinfunction "12_12") (pintype "passive"))
      (node (ref "IC7") (pin "98") (pinfunction "GPIO_AD_B0_10_98") (pintype "bidirectional"))
    )
    (net (code "96") (name "/UART1_RX") (class "Default")
      (node (ref "H1") (pin "4") (pinfunction "4_4") (pintype "passive"))
      (node (ref "IC7") (pin "101") (pinfunction "GPIO_AD_B0_07_101") (pintype "bidirectional"))
    )
    (net (code "97") (name "/UART1_TX") (class "Default")
      (node (ref "H1") (pin "2") (pinfunction "2_2") (pintype "passive"))
      (node (ref "IC7") (pin "105") (pinfunction "GPIO_AD_B0_06_105") (pintype "bidirectional"))
    )
    (net (code "98") (name "/UART3_RX") (class "Default")
      (node (ref "H1") (pin "52") (pinfunction "52_52") (pintype "passive"))
      (node (ref "IC7") (pin "93") (pinfunction "GPIO_AD_B0_15_93") (pintype "bidirectional"))
    )
    (net (code "99") (name "/UART3_TX") (class "Default")
      (node (ref "H1") (pin "50") (pinfunction "50_50") (pintype "passive"))
      (node (ref "IC7") (pin "94") (pinfunction "GPIO_AD_B0_14_94") (pintype "bidirectional"))
    )
    (net (code "100") (name "/UART4_RX") (class "Default")
      (node (ref "H1") (pin "3") (pinfunction "3_3") (pintype "passive"))
      (node (ref "IC7") (pin "79") (pinfunction "GPIO_AD_B1_11_79") (pintype "bidirectional"))
    )
    (net (code "101") (name "/UART4_TX") (class "Default")
      (node (ref "H1") (pin "1") (pinfunction "1_1") (pintype "passive"))
      (node (ref "IC7") (pin "80") (pinfunction "GPIO_AD_B1_10_80") (pintype "bidirectional"))
    )
    (net (code "102") (name "/USB_OTG1_CHD") (class "Default")
      (node (ref "IC7") (pin "66") (pinfunction "USB_OTG1_CHD_B_66") (pintype "bidirectional"))
      (node (ref "TP5") (pin "TP") (pinfunction "TP_TP") (pintype "input"))
    )
    (net (code "103") (name "/VDD_HIGH_CAP") (class "Default")
      (node (ref "C23") (pin "2") (pinfunction "2_2") (pintype "passive"))
      (node (ref "C24") (pin "2") (pinfunction "2_2") (pintype "passive"))
      (node (ref "IC7") (pin "65") (pinfunction "VDD_HIGH_CAP_65") (pintype "bidirectional"))
    )
    (net (code "104") (name "/VDD_SNVS_CAP") (class "Default")
      (node (ref "C21") (pin "2") (pinfunction "2_2") (pintype "passive"))
      (node (ref "IC7") (pin "56") (pinfunction "VDD_SNVS_CAP_56") (pintype "bidirectional"))
    )
    (net (code "105") (name "/VDD_USB_3V") (class "Default")
      (node (ref "C14") (pin "2") (pinfunction "2_2") (pintype "passive"))
      (node (ref "C4") (pin "2") (pinfunction "2_2") (pintype "passive"))
      (node (ref "IC7") (pin "61") (pinfunction "VDD_USB_CAP_61") (pintype "bidirectional"))
    )
    (net (code "106") (name "/VSD_3V3") (class "Default")
      (node (ref "C38") (pin "2") (pinfunction "2_2") (pintype "passive"))
      (node (ref "C49") (pin "2") (pinfunction "2_2") (pintype "passive"))
      (node (ref "C52") (pin "2") (pinfunction "2_2") (pintype "passive"))
      (node (ref "IC8") (pin "3") (pinfunction "VOUT_3") (pintype "bidirectional"))
      (node (ref "J1") (pin "4") (pinfunction "VDD_4") (pintype "power_in"))
    )
    (net (code "107") (name "/WAKEUP") (class "Default")
      (node (ref "IC7") (pin "52") (pinfunction "WAKEUP_52") (pintype "bidirectional"))
      (node (ref "TP8") (pin "TP") (pinfunction "TP_TP") (pintype "input"))
    )
    (net (code "108") (name "/XTALI") (class "Default")
      (node (ref "C39") (pin "2") (pinfunction "2_2") (pintype "passive"))
      (node (ref "IC7") (pin "67") (pinfunction "XTALI_67") (pintype "bidirectional"))
      (node (ref "R10") (pin "1") (pinfunction "1_1") (pintype "passive"))
      (node (ref "Y1") (pin "3") (pinfunction "XTAL_2_3") (pintype "bidirectional"))
    )
    (net (code "109") (name "/XTALO") (class "Default")
      (node (ref "C40") (pin "2") (pinfunction "2_2") (pintype "passive"))
      (node (ref "IC7") (pin "68") (pinfunction "XTALO_68") (pintype "bidirectional"))
      (node (ref "Y1") (pin "1") (pinfunction "XTAL_1_1") (pintype "bidirectional"))
    )
    (net (code "110") (name "GND") (class "Default")
      (node (ref "C1") (pin "1") (pinfunction "1_1") (pintype "passive"))
      (node (ref "C10") (pin "2") (pinfunction "2_2") (pintype "passive"))
      (node (ref "C11") (pin "2") (pinfunction "2_2") (pintype "passive"))
      (node (ref "C12") (pin "2") (pinfunction "2_2") (pintype "passive"))
      (node (ref "C13") (pin "2") (pinfunction "2_2") (pintype "passive"))
      (node (ref "C14") (pin "1") (pinfunction "1_1") (pintype "passive"))
      (node (ref "C15") (pin "1") (pinfunction "1_1") (pintype "passive"))
      (node (ref "C16") (pin "1") (pinfunction "1_1") (pintype "passive"))
      (node (ref "C17") (pin "1") (pinfunction "1_1") (pintype "passive"))
      (node (ref "C18") (pin "1") (pinfunction "1_1") (pintype "passive"))
      (node (ref "C19") (pin "1") (pinfunction "1_1") (pintype "passive"))
      (node (ref "C2") (pin "1") (pinfunction "1_1") (pintype "passive"))
      (node (ref "C20") (pin "1") (pinfunction "1_1") (pintype "passive"))
      (node (ref "C21") (pin "1") (pinfunction "1_1") (pintype "passive"))
      (node (ref "C22") (pin "1") (pinfunction "1_1") (pintype "passive"))
      (node (ref "C23") (pin "1") (pinfunction "1_1") (pintype "passive"))
      (node (ref "C24") (pin "1") (pinfunction "1_1") (pintype "passive"))
      (node (ref "C25") (pin "1") (pinfunction "1_1") (pintype "passive"))
      (node (ref "C26") (pin "1") (pinfunction "1_1") (pintype "passive"))
      (node (ref "C27") (pin "1") (pinfunction "1_1") (pintype "passive"))
      (node (ref "C28") (pin "1") (pinfunction "1_1") (pintype "passive"))
      (node (ref "C29") (pin "1") (pinfunction "1_1") (pintype "passive"))
      (node (ref "C3") (pin "1") (pinfunction "1_1") (pintype "passive"))
      (node (ref "C30") (pin "1") (pinfunction "1_1") (pintype "passive"))
      (node (ref "C31") (pin "1") (pinfunction "1_1") (pintype "passive"))
      (node (ref "C32") (pin "1") (pinfunction "1_1") (pintype "passive"))
      (node (ref "C33") (pin "1") (pinfunction "1_1") (pintype "passive"))
      (node (ref "C34") (pin "1") (pinfunction "1_1") (pintype "passive"))
      (node (ref "C35") (pin "1") (pinfunction "1_1") (pintype "passive"))
      (node (ref "C36") (pin "1") (pinfunction "1_1") (pintype "passive"))
      (node (ref "C37") (pin "1") (pinfunction "1_1") (pintype "passive"))
      (node (ref "C38") (pin "1") (pinfunction "1_1") (pintype "passive"))
      (node (ref "C39") (pin "1") (pinfunction "1_1") (pintype "passive"))
      (node (ref "C4") (pin "1") (pinfunction "1_1") (pintype "passive"))
      (node (ref "C40") (pin "1") (pinfunction "1_1") (pintype "passive"))
      (node (ref "C41") (pin "1") (pinfunction "1_1") (pintype "passive"))
      (node (ref "C42") (pin "1") (pinfunction "1_1") (pintype "passive"))
      (node (ref "C43") (pin "1") (pinfunction "1_1") (pintype "passive"))
      (node (ref "C44") (pin "1") (pinfunction "1_1") (pintype "passive"))
      (node (ref "C45") (pin "1") (pinfunction "1_1") (pintype "passive"))
      (node (ref "C46") (pin "1") (pinfunction "1_1") (pintype "passive"))
      (node (ref "C47") (pin "1") (pinfunction "1_1") (pintype "passive"))
      (node (ref "C48") (pin "1") (pinfunction "1_1") (pintype "passive"))
      (node (ref "C49") (pin "1") (pinfunction "1_1") (pintype "passive"))
      (node (ref "C5") (pin "1") (pinfunction "1_1") (pintype "passive"))
      (node (ref "C50") (pin "1") (pinfunction "1_1") (pintype "passive"))
      (node (ref "C51") (pin "1") (pinfunction "1_1") (pintype "passive"))
      (node (ref "C52") (pin "1") (pinfunction "1_1") (pintype "passive"))
      (node (ref "C53") (pin "1") (pinfunction "1_1") (pintype "passive"))
      (node (ref "C54") (pin "1") (pinfunction "1_1") (pintype "passive"))
      (node (ref "C55") (pin "1") (pinfunction "1_1") (pintype "passive"))
      (node (ref "C56") (pin "1") (pinfunction "1_1") (pintype "passive"))
      (node (ref "C57") (pin "1") (pinfunction "1_1") (pintype "passive"))
      (node (ref "C58") (pin "1") (pinfunction "1_1") (pintype "passive"))
      (node (ref "C59") (pin "1") (pinfunction "1_1") (pintype "passive"))
      (node (ref "C6") (pin "2") (pinfunction "2_2") (pintype "passive"))
      (node (ref "C60") (pin "1") (pinfunction "1_1") (pintype "passive"))
      (node (ref "C61") (pin "1") (pinfunction "1_1") (pintype "passive"))
      (node (ref "C62") (pin "1") (pinfunction "1_1") (pintype "passive"))
      (node (ref "C63") (pin "1") (pinfunction "1_1") (pintype "passive"))
      (node (ref "C64") (pin "1") (pinfunction "1_1") (pintype "passive"))
      (node (ref "C7") (pin "2") (pinfunction "2_2") (pintype "passive"))
      (node (ref "C8") (pin "2") (pinfunction "2_2") (pintype "passive"))
      (node (ref "C9") (pin "2") (pinfunction "2_2") (pintype "passive"))
      (node (ref "H2") (pin "10") (pinfunction "10_10") (pintype "passive"))
      (node (ref "H2") (pin "13") (pinfunction "13_13") (pintype "passive"))
      (node (ref "H2") (pin "18") (pinfunction "18_18") (pintype "passive"))
      (node (ref "H2") (pin "21") (pinfunction "21_21") (pintype "passive"))
      (node (ref "H2") (pin "22") (pinfunction "22_22") (pintype "passive"))
      (node (ref "H2") (pin "29") (pinfunction "29_29") (pintype "passive"))
      (node (ref "H2") (pin "30") (pinfunction "30_30") (pintype "passive"))
      (node (ref "H2") (pin "31") (pinfunction "31_31") (pintype "passive"))
      (node (ref "H2") (pin "47") (pinfunction "47_47") (pintype "passive"))
      (node (ref "H2") (pin "48") (pinfunction "48_48") (pintype "passive"))
      (node (ref "IC1") (pin "1") (pinfunction "GND_1") (pintype "bidirectional"))
      (node (ref "IC10") (pin "4") (pinfunction "GND_4") (pintype "bidirectional"))
      (node (ref "IC7") (pin "103") (pinfunction "VSS_6_103") (pintype "bidirectional"))
      (node (ref "IC7") (pin "113") (pinfunction "VSS_7_113") (pintype "bidirectional"))
      (node (ref "IC7") (pin "135") (pinfunction "VSS_8_135") (pintype "bidirectional"))
      (node (ref "IC7") (pin "35") (pinfunction "DCDC_GND_35") (pintype "bidirectional"))
      (node (ref "IC7") (pin "40") (pinfunction "VSS_2_40") (pintype "bidirectional"))
      (node (ref "IC7") (pin "51") (pinfunction "TEST_MODE_51") (pintype "bidirectional"))
      (node (ref "IC7") (pin "6") (pinfunction "VSS_1_6") (pintype "bidirectional"))
      (node (ref "IC7") (pin "60") (pinfunction "VSS_3_60") (pintype "bidirectional"))
      (node (ref "IC7") (pin "64") (pinfunction "NGND_KEL0_64") (pintype "bidirectional"))
      (node (ref "IC7") (pin "70") (pinfunction "VSS_4_70") (pintype "bidirectional"))
      (node (ref "IC7") (pin "85") (pinfunction "VSS_5_85") (pintype "bidirectional"))
      (node (ref "IC8") (pin "2") (pinfunction "GND_2") (pintype "bidirectional"))
      (node (ref "IC8") (pin "5") (pinfunction "EP_5") (pintype "bidirectional"))
      (node (ref "IC9") (pin "12") (pinfunction "VSSQ_2_12") (pintype "bidirectional"))
      (node (ref "IC9") (pin "28") (pinfunction "VSS_1_28") (pintype "bidirectional"))
      (node (ref "IC9") (pin "41") (pinfunction "VSS_2_41") (pintype "bidirectional"))
      (node (ref "IC9") (pin "46") (pinfunction "VSSQ_3_46") (pintype "bidirectional"))
      (node (ref "IC9") (pin "52") (pinfunction "VSSQ_4_52") (pintype "bidirectional"))
      (node (ref "IC9") (pin "54") (pinfunction "VSS_3_54") (pintype "bidirectional"))
      (node (ref "IC9") (pin "6") (pinfunction "VSSQ_1_6") (pintype "bidirectional"))
      (node (ref "J1") (pin "10") (pinfunction "10_10") (pintype "bidirectional"))
      (node (ref "J1") (pin "11") (pinfunction "11_11") (pintype "bidirectional"))
      (node (ref "J1") (pin "12") (pinfunction "12_12") (pintype "bidirectional"))
      (node (ref "J1") (pin "13") (pinfunction "13_13") (pintype "bidirectional"))
      (node (ref "J1") (pin "14") (pinfunction "14_14") (pintype "bidirectional"))
      (node (ref "J1") (pin "15") (pinfunction "15_15") (pintype "bidirectional"))
      (node (ref "J1") (pin "16") (pinfunction "16_16") (pintype "bidirectional"))
      (node (ref "J1") (pin "6") (pinfunction "VSS_6") (pintype "power_in"))
      (node (ref "J2") (pin "10") (pinfunction "10_10") (pintype "bidirectional"))
      (node (ref "J2") (pin "12") (pinfunction "12_12") (pintype "bidirectional"))
      (node (ref "J2") (pin "4") (pinfunction "4_4") (pintype "bidirectional"))
      (node (ref "J2") (pin "6") (pinfunction "6_6") (pintype "bidirectional"))
      (node (ref "J2") (pin "8") (pinfunction "8_8") (pintype "bidirectional"))
      (node (ref "PS1") (pin "2") (pinfunction "2_2") (pintype "bidirectional"))
      (node (ref "R10") (pin "2") (pinfunction "2_2") (pintype "passive"))
      (node (ref "R2") (pin "1") (pinfunction "1_1") (pintype "passive"))
      (node (ref "R26") (pin "2") (pinfunction "2_2") (pintype "passive"))
      (node (ref "R64") (pin "1") (pinfunction "1_1") (pintype "passive"))
      (node (ref "R65") (pin "1") (pinfunction "1_1") (pintype "passive"))
      (node (ref "R66") (pin "1") (pinfunction "1_1") (pintype "passive"))
      (node (ref "R67") (pin "1") (pinfunction "1_1") (pintype "passive"))
      (node (ref "Y1") (pin "2") (pinfunction "NC_1_2") (pintype "bidirectional"))
      (node (ref "Y1") (pin "4") (pinfunction "NC_2_4") (pintype "bidirectional"))
    )
    (net (code "111") (name "Net-(D1-K)") (class "Default")
      (node (ref "C20") (pin "2") (pinfunction "2_2") (pintype "passive"))
      (node (ref "D1") (pin "1") (pinfunction "K_1") (pintype "bidirectional"))
      (node (ref "IC7") (pin "55") (pinfunction "VDD_SNVS_IN_55") (pintype "bidirectional"))
    )
    (net (code "112") (name "Net-(IC1-VDD)") (class "Default")
      (node (ref "IC1") (pin "3") (pinfunction "VDD_3") (pintype "bidirectional"))
      (node (ref "R9") (pin "2") (pinfunction "2_2") (pintype "passive"))
    )
    (net (code "113") (name "Net-(IC7-DCDC_LP)") (class "Default")
      (node (ref "IC7") (pin "36") (pinfunction "DCDC_LP_36") (pintype "bidirectional"))
      (node (ref "L2") (pin "2") (pinfunction "2_2") (pintype "bidirectional"))
    )
    (net (code "114") (name "Net-(IC7-DCDC_PSWITCH)") (class "Default")
      (node (ref "C44") (pin "2") (pinfunction "2_2") (pintype "passive"))
      (node (ref "IC7") (pin "37") (pinfunction "DCDC_PSWITCH_37") (pintype "bidirectional"))
      (node (ref "R11") (pin "1") (pinfunction "1_1") (pintype "passive"))
    )
    (net (code "115") (name "Net-(J2-Pad1)") (class "Default")
      (node (ref "J2") (pin "1") (pinfunction "1_1") (pintype "bidirectional"))
      (node (ref "R27") (pin "2") (pinfunction "2_2") (pintype "passive"))
    )
    (net (code "116") (name "unconnected-(H1-Pad6)") (class "Default")
      (node (ref "H1") (pin "6") (pinfunction "6_6") (pintype "passive"))
    )
    (net (code "117") (name "unconnected-(H1-Pad11)") (class "Default")
      (node (ref "H1") (pin "11") (pinfunction "11_11") (pintype "passive"))
    )
    (net (code "118") (name "unconnected-(H1-Pad13)") (class "Default")
      (node (ref "H1") (pin "13") (pinfunction "13_13") (pintype "passive"))
    )
    (net (code "119") (name "unconnected-(H1-Pad14)") (class "Default")
      (node (ref "H1") (pin "14") (pinfunction "14_14") (pintype "passive"))
    )
    (net (code "120") (name "unconnected-(H1-Pad15)") (class "Default")
      (node (ref "H1") (pin "15") (pinfunction "15_15") (pintype "passive"))
    )
    (net (code "121") (name "unconnected-(H1-Pad17)") (class "Default")
      (node (ref "H1") (pin "17") (pinfunction "17_17") (pintype "passive"))
    )
    (net (code "122") (name "unconnected-(H1-Pad24)") (class "Default")
      (node (ref "H1") (pin "24") (pinfunction "24_24") (pintype "passive"))
    )
    (net (code "123") (name "unconnected-(H1-Pad26)") (class "Default")
      (node (ref "H1") (pin "26") (pinfunction "26_26") (pintype "passive"))
    )
    (net (code "124") (name "unconnected-(H1-Pad27)") (class "Default")
      (node (ref "H1") (pin "27") (pinfunction "27_27") (pintype "passive"))
    )
    (net (code "125") (name "unconnected-(H1-Pad28)") (class "Default")
      (node (ref "H1") (pin "28") (pinfunction "28_28") (pintype "passive"))
    )
    (net (code "126") (name "unconnected-(H1-Pad29)") (class "Default")
      (node (ref "H1") (pin "29") (pinfunction "29_29") (pintype "passive"))
    )
    (net (code "127") (name "unconnected-(H1-Pad30)") (class "Default")
      (node (ref "H1") (pin "30") (pinfunction "30_30") (pintype "passive"))
    )
    (net (code "128") (name "unconnected-(H1-Pad31)") (class "Default")
      (node (ref "H1") (pin "31") (pinfunction "31_31") (pintype "passive"))
    )
    (net (code "129") (name "unconnected-(H1-Pad32)") (class "Default")
      (node (ref "H1") (pin "32") (pinfunction "32_32") (pintype "passive"))
    )
    (net (code "130") (name "unconnected-(H1-Pad33)") (class "Default")
      (node (ref "H1") (pin "33") (pinfunction "33_33") (pintype "passive"))
    )
    (net (code "131") (name "unconnected-(H1-Pad34)") (class "Default")
      (node (ref "H1") (pin "34") (pinfunction "34_34") (pintype "passive"))
    )
    (net (code "132") (name "unconnected-(H1-Pad36)") (class "Default")
      (node (ref "H1") (pin "36") (pinfunction "36_36") (pintype "passive"))
    )
    (net (code "133") (name "unconnected-(H1-Pad38)") (class "Default")
      (node (ref "H1") (pin "38") (pinfunction "38_38") (pintype "passive"))
    )
    (net (code "134") (name "unconnected-(H1-Pad39)") (class "Default")
      (node (ref "H1") (pin "39") (pinfunction "39_39") (pintype "passive"))
    )
    (net (code "135") (name "unconnected-(H1-Pad40)") (class "Default")
      (node (ref "H1") (pin "40") (pinfunction "40_40") (pintype "passive"))
    )
    (net (code "136") (name "unconnected-(H1-Pad41)") (class "Default")
      (node (ref "H1") (pin "41") (pinfunction "41_41") (pintype "passive"))
    )
    (net (code "137") (name "unconnected-(H1-Pad43)") (class "Default")
      (node (ref "H1") (pin "43") (pinfunction "43_43") (pintype "passive"))
    )
    (net (code "138") (name "unconnected-(H1-Pad45)") (class "Default")
      (node (ref "H1") (pin "45") (pinfunction "45_45") (pintype "passive"))
    )
    (net (code "139") (name "unconnected-(H1-Pad46)") (class "Default")
      (node (ref "H1") (pin "46") (pinfunction "46_46") (pintype "passive"))
    )
    (net (code "140") (name "unconnected-(H1-Pad47)") (class "Default")
      (node (ref "H1") (pin "47") (pinfunction "47_47") (pintype "passive"))
    )
    (net (code "141") (name "unconnected-(H1-Pad48)") (class "Default")
      (node (ref "H1") (pin "48") (pinfunction "48_48") (pintype "passive"))
    )
    (net (code "142") (name "unconnected-(H2-Pad1)") (class "Default")
      (node (ref "H2") (pin "1") (pinfunction "1_1") (pintype "passive"))
    )
    (net (code "143") (name "unconnected-(H2-Pad2)") (class "Default")
      (node (ref "H2") (pin "2") (pinfunction "2_2") (pintype "passive"))
    )
    (net (code "144") (name "unconnected-(H2-Pad3)") (class "Default")
      (node (ref "H2") (pin "3") (pinfunction "3_3") (pintype "passive"))
    )
    (net (code "145") (name "unconnected-(H2-Pad4)") (class "Default")
      (node (ref "H2") (pin "4") (pinfunction "4_4") (pintype "passive"))
    )
    (net (code "146") (name "unconnected-(H2-Pad5)") (class "Default")
      (node (ref "H2") (pin "5") (pinfunction "5_5") (pintype "passive"))
    )
    (net (code "147") (name "unconnected-(H2-Pad6)") (class "Default")
      (node (ref "H2") (pin "6") (pinfunction "6_6") (pintype "passive"))
    )
    (net (code "148") (name "unconnected-(H2-Pad7)") (class "Default")
      (node (ref "H2") (pin "7") (pinfunction "7_7") (pintype "passive"))
    )
    (net (code "149") (name "unconnected-(H2-Pad8)") (class "Default")
      (node (ref "H2") (pin "8") (pinfunction "8_8") (pintype "passive"))
    )
    (net (code "150") (name "unconnected-(H2-Pad9)") (class "Default")
      (node (ref "H2") (pin "9") (pinfunction "9_9") (pintype "passive"))
    )
    (net (code "151") (name "unconnected-(H2-Pad11)") (class "Default")
      (node (ref "H2") (pin "11") (pinfunction "11_11") (pintype "passive"))
    )
    (net (code "152") (name "unconnected-(H2-Pad12)") (class "Default")
      (node (ref "H2") (pin "12") (pinfunction "12_12") (pintype "passive"))
    )
    (net (code "153") (name "unconnected-(H2-Pad14)") (class "Default")
      (node (ref "H2") (pin "14") (pinfunction "14_14") (pintype "passive"))
    )
    (net (code "154") (name "unconnected-(H2-Pad15)") (class "Default")
      (node (ref "H2") (pin "15") (pinfunction "15_15") (pintype "passive"))
    )
    (net (code "155") (name "unconnected-(H2-Pad16)") (class "Default")
      (node (ref "H2") (pin "16") (pinfunction "16_16") (pintype "passive"))
    )
    (net (code "156") (name "unconnected-(H2-Pad17)") (class "Default")
      (node (ref "H2") (pin "17") (pinfunction "17_17") (pintype "passive"))
    )
    (net (code "157") (name "unconnected-(H2-Pad19)") (class "Default")
      (node (ref "H2") (pin "19") (pinfunction "19_19") (pintype "passive"))
    )
    (net (code "158") (name "unconnected-(H2-Pad20)") (class "Default")
      (node (ref "H2") (pin "20") (pinfunction "20_20") (pintype "passive"))
    )
    (net (code "159") (name "unconnected-(H2-Pad23)") (class "Default")
      (node (ref "H2") (pin "23") (pinfunction "23_23") (pintype "passive"))
    )
    (net (code "160") (name "unconnected-(H2-Pad24)") (class "Default")
      (node (ref "H2") (pin "24") (pinfunction "24_24") (pintype "passive"))
    )
    (net (code "161") (name "unconnected-(H2-Pad25)") (class "Default")
      (node (ref "H2") (pin "25") (pinfunction "25_25") (pintype "passive"))
    )
    (net (code "162") (name "unconnected-(H2-Pad26)") (class "Default")
      (node (ref "H2") (pin "26") (pinfunction "26_26") (pintype "passive"))
    )
    (net (code "163") (name "unconnected-(H2-Pad32)") (class "Default")
      (node (ref "H2") (pin "32") (pinfunction "32_32") (pintype "passive"))
    )
    (net (code "164") (name "unconnected-(H2-Pad33)") (class "Default")
      (node (ref "H2") (pin "33") (pinfunction "33_33") (pintype "passive"))
    )
    (net (code "165") (name "unconnected-(H2-Pad34)") (class "Default")
      (node (ref "H2") (pin "34") (pinfunction "34_34") (pintype "passive"))
    )
    (net (code "166") (name "unconnected-(H2-Pad35)") (class "Default")
      (node (ref "H2") (pin "35") (pinfunction "35_35") (pintype "passive"))
    )
    (net (code "167") (name "unconnected-(H2-Pad36)") (class "Default")
      (node (ref "H2") (pin "36") (pinfunction "36_36") (pintype "passive"))
    )
    (net (code "168") (name "unconnected-(H2-Pad37)") (class "Default")
      (node (ref "H2") (pin "37") (pinfunction "37_37") (pintype "passive"))
    )
    (net (code "169") (name "unconnected-(H2-Pad38)") (class "Default")
      (node (ref "H2") (pin "38") (pinfunction "38_38") (pintype "passive"))
    )
    (net (code "170") (name "unconnected-(H2-Pad39)") (class "Default")
      (node (ref "H2") (pin "39") (pinfunction "39_39") (pintype "passive"))
    )
    (net (code "171") (name "unconnected-(H2-Pad40)") (class "Default")
      (node (ref "H2") (pin "40") (pinfunction "40_40") (pintype "passive"))
    )
    (net (code "172") (name "unconnected-(H2-Pad41)") (class "Default")
      (node (ref "H2") (pin "41") (pinfunction "41_41") (pintype "passive"))
    )
    (net (code "173") (name "unconnected-(H2-Pad42)") (class "Default")
      (node (ref "H2") (pin "42") (pinfunction "42_42") (pintype "passive"))
    )
    (net (code "174") (name "unconnected-(H2-Pad43)") (class "Default")
      (node (ref "H2") (pin "43") (pinfunction "43_43") (pintype "passive"))
    )
    (net (code "175") (name "unconnected-(H2-Pad44)") (class "Default")
      (node (ref "H2") (pin "44") (pinfunction "44_44") (pintype "passive"))
    )
    (net (code "176") (name "unconnected-(H2-Pad45)") (class "Default")
      (node (ref "H2") (pin "45") (pinfunction "45_45") (pintype "passive"))
    )
    (net (code "177") (name "unconnected-(H2-Pad46)") (class "Default")
      (node (ref "H2") (pin "46") (pinfunction "46_46") (pintype "passive"))
    )
    (net (code "178") (name "unconnected-(H2-Pad49)") (class "Default")
      (node (ref "H2") (pin "49") (pinfunction "49_49") (pintype "passive"))
    )
    (net (code "179") (name "unconnected-(H2-Pad50)") (class "Default")
      (node (ref "H2") (pin "50") (pinfunction "50_50") (pintype "passive"))
    )
    (net (code "180") (name "unconnected-(H2-Pad51)") (class "Default")
      (node (ref "H2") (pin "51") (pinfunction "51_51") (pintype "passive"))
    )
    (net (code "181") (name "unconnected-(IC7-GPIO_AD_B1_13-Pad76)") (class "Default")
      (node (ref "IC7") (pin "76") (pinfunction "GPIO_AD_B1_13_76") (pintype "bidirectional"))
    )
    (net (code "182") (name "unconnected-(IC7-GPIO_EMC_28-Pad128)") (class "Default")
      (node (ref "IC7") (pin "128") (pinfunction "GPIO_EMC_28_128") (pintype "bidirectional"))
    )
    (net (code "183") (name "unconnected-(IC7-GPIO_EMC_40-Pad116)") (class "Default")
      (node (ref "IC7") (pin "116") (pinfunction "GPIO_EMC_40_116") (pintype "bidirectional"))
    )
    (net (code "184") (name "unconnected-(IC7-GPIO_EMC_41-Pad115)") (class "Default")
      (node (ref "IC7") (pin "115") (pinfunction "GPIO_EMC_41_115") (pintype "bidirectional"))
    )
    (net (code "185") (name "unconnected-(IC7-GPIO_SD_B1_00-Pad33)") (class "Default")
      (node (ref "IC7") (pin "33") (pinfunction "GPIO_SD_B1_00_33") (pintype "bidirectional"))
    )
    (net (code "186") (name "unconnected-(IC7-GPIO_SD_B1_01-Pad32)") (class "Default")
      (node (ref "IC7") (pin "32") (pinfunction "GPIO_SD_B1_01_32") (pintype "bidirectional"))
    )
    (net (code "187") (name "unconnected-(IC7-GPIO_SD_B1_02-Pad30)") (class "Default")
      (node (ref "IC7") (pin "30") (pinfunction "GPIO_SD_B1_02_30") (pintype "bidirectional"))
    )
    (net (code "188") (name "unconnected-(IC7-GPIO_SD_B1_03-Pad28)") (class "Default")
      (node (ref "IC7") (pin "28") (pinfunction "GPIO_SD_B1_03_28") (pintype "bidirectional"))
    )
    (net (code "189") (name "unconnected-(IC7-ONOFF-Pad49)") (class "Default")
      (node (ref "IC7") (pin "49") (pinfunction "ONOFF_49") (pintype "bidirectional"))
    )
    (net (code "190") (name "unconnected-(IC7-PMIC_ON_REQ-Pad53)") (class "Default")
      (node (ref "IC7") (pin "53") (pinfunction "PMIC_ON_REQ_53") (pintype "bidirectional"))
    )
    (net (code "191") (name "unconnected-(IC7-USB_OTG1_DN-Pad62)") (class "Default")
      (node (ref "IC7") (pin "62") (pinfunction "USB_OTG1_DN_62") (pintype "bidirectional"))
    )
    (net (code "192") (name "unconnected-(IC7-USB_OTG1_DP-Pad63)") (class "Default")
      (node (ref "IC7") (pin "63") (pinfunction "USB_OTG1_DP_63") (pintype "bidirectional"))
    )
    (net (code "193") (name "unconnected-(IC9-NC_6-Pad40)") (class "Default")
      (node (ref "IC9") (pin "40") (pinfunction "NC_6_40") (pintype "bidirectional"))
    )
    (net (code "194") (name "unconnected-(J2-Pad14)") (class "Default")
      (node (ref "J2") (pin "14") (pinfunction "14_14") (pintype "bidirectional"))
    )
    (net (code "195") (name "unconnected-(J2-Pad16)") (class "Default")
      (node (ref "J2") (pin "16") (pinfunction "16_16") (pintype "bidirectional"))
    )
    (net (code "196") (name "unconnected-(J2-Pad18)") (class "Default")
      (node (ref "J2") (pin "18") (pinfunction "18_18") (pintype "bidirectional"))
    )
    (net (code "197") (name "unconnected-(J2-Pad19)") (class "Default")
      (node (ref "J2") (pin "19") (pinfunction "19_19") (pintype "bidirectional"))
    )
    (net (code "198") (name "unconnected-(PS1-Pad3)") (class "Default")
      (node (ref "PS1") (pin "3") (pinfunction "3_3") (pintype "bidirectional"))
    )
  )
)
